# Control.net
KiCad netlist of a schematic drawn in EAGLE
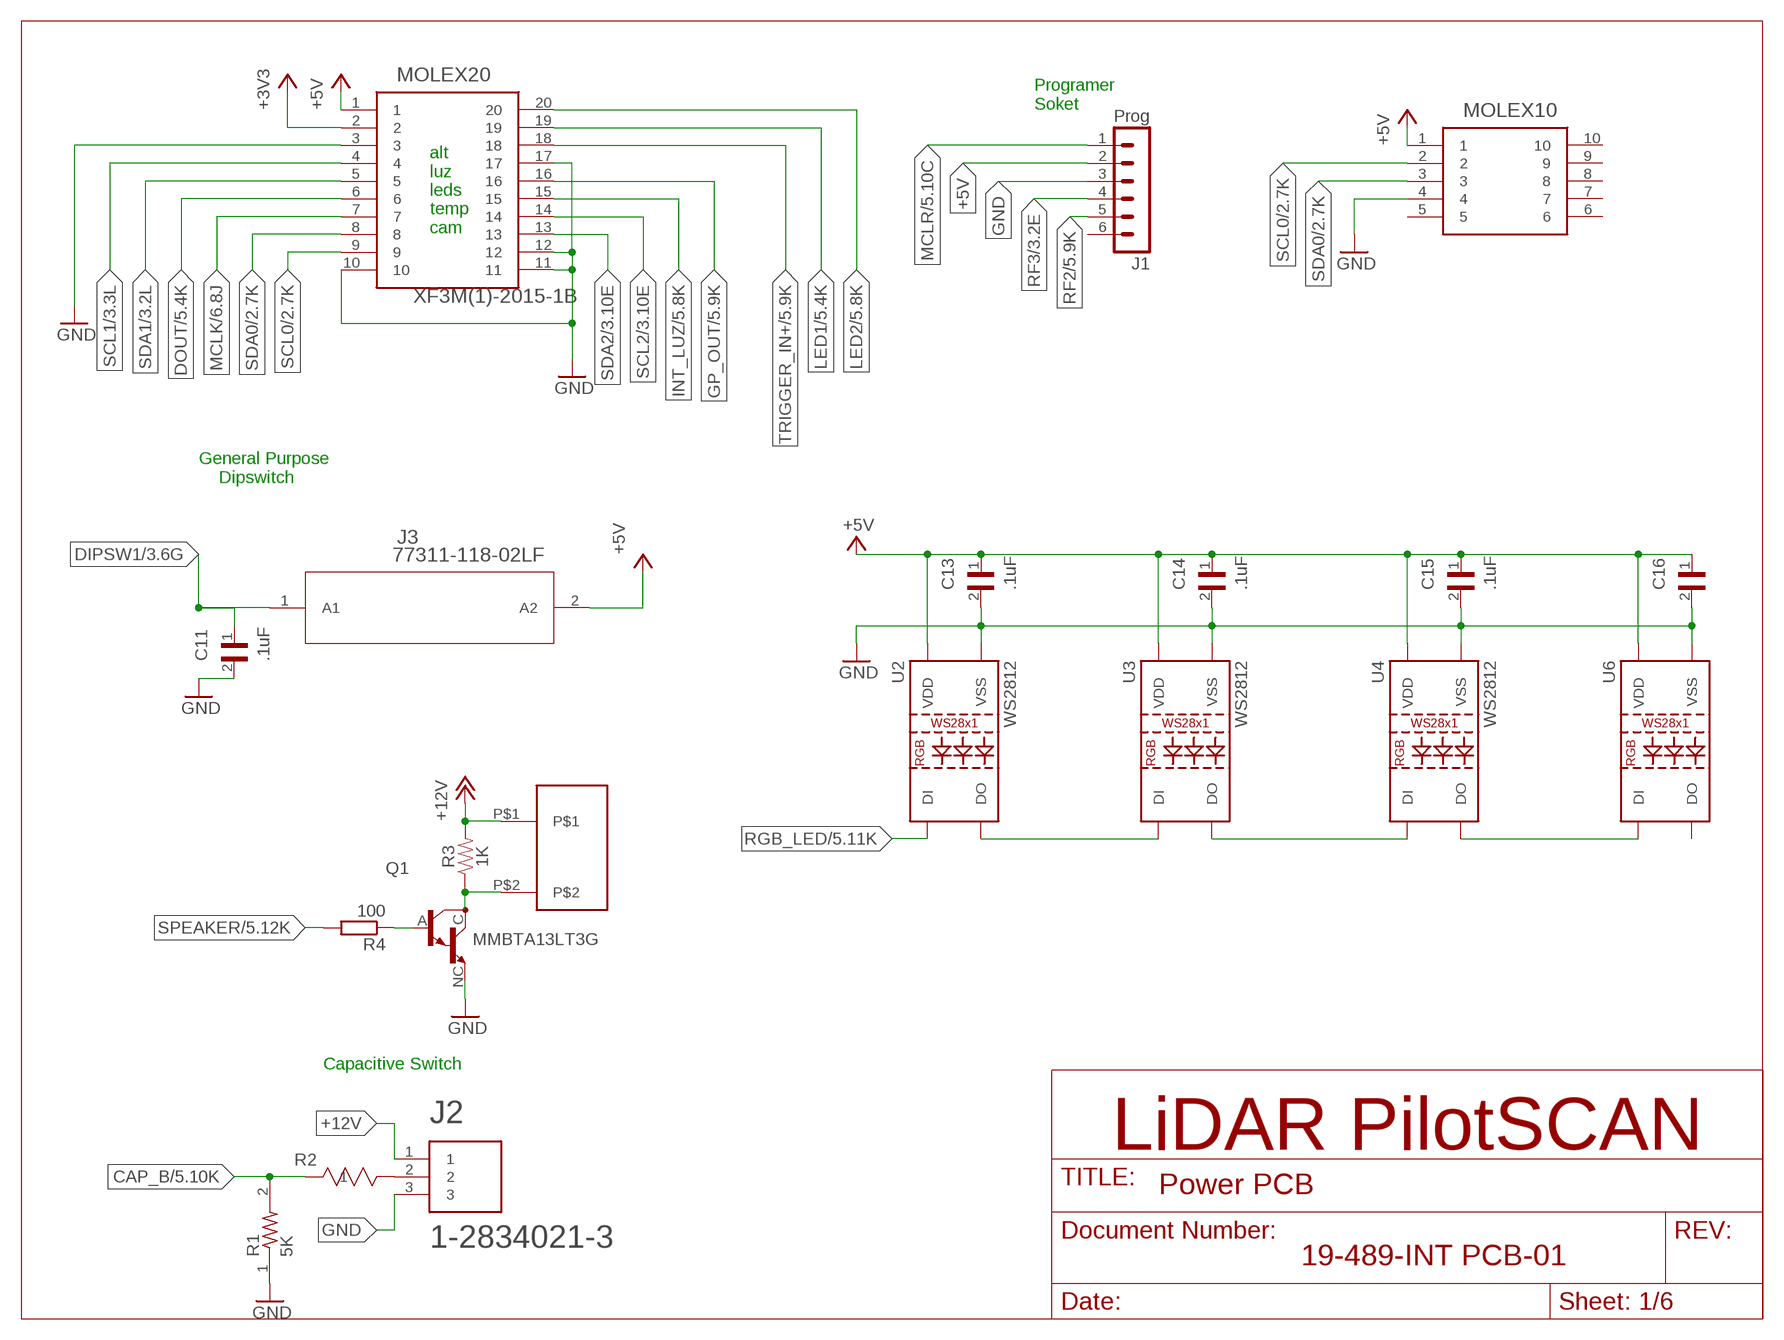
[diagram p0: schematic, sheet 1]
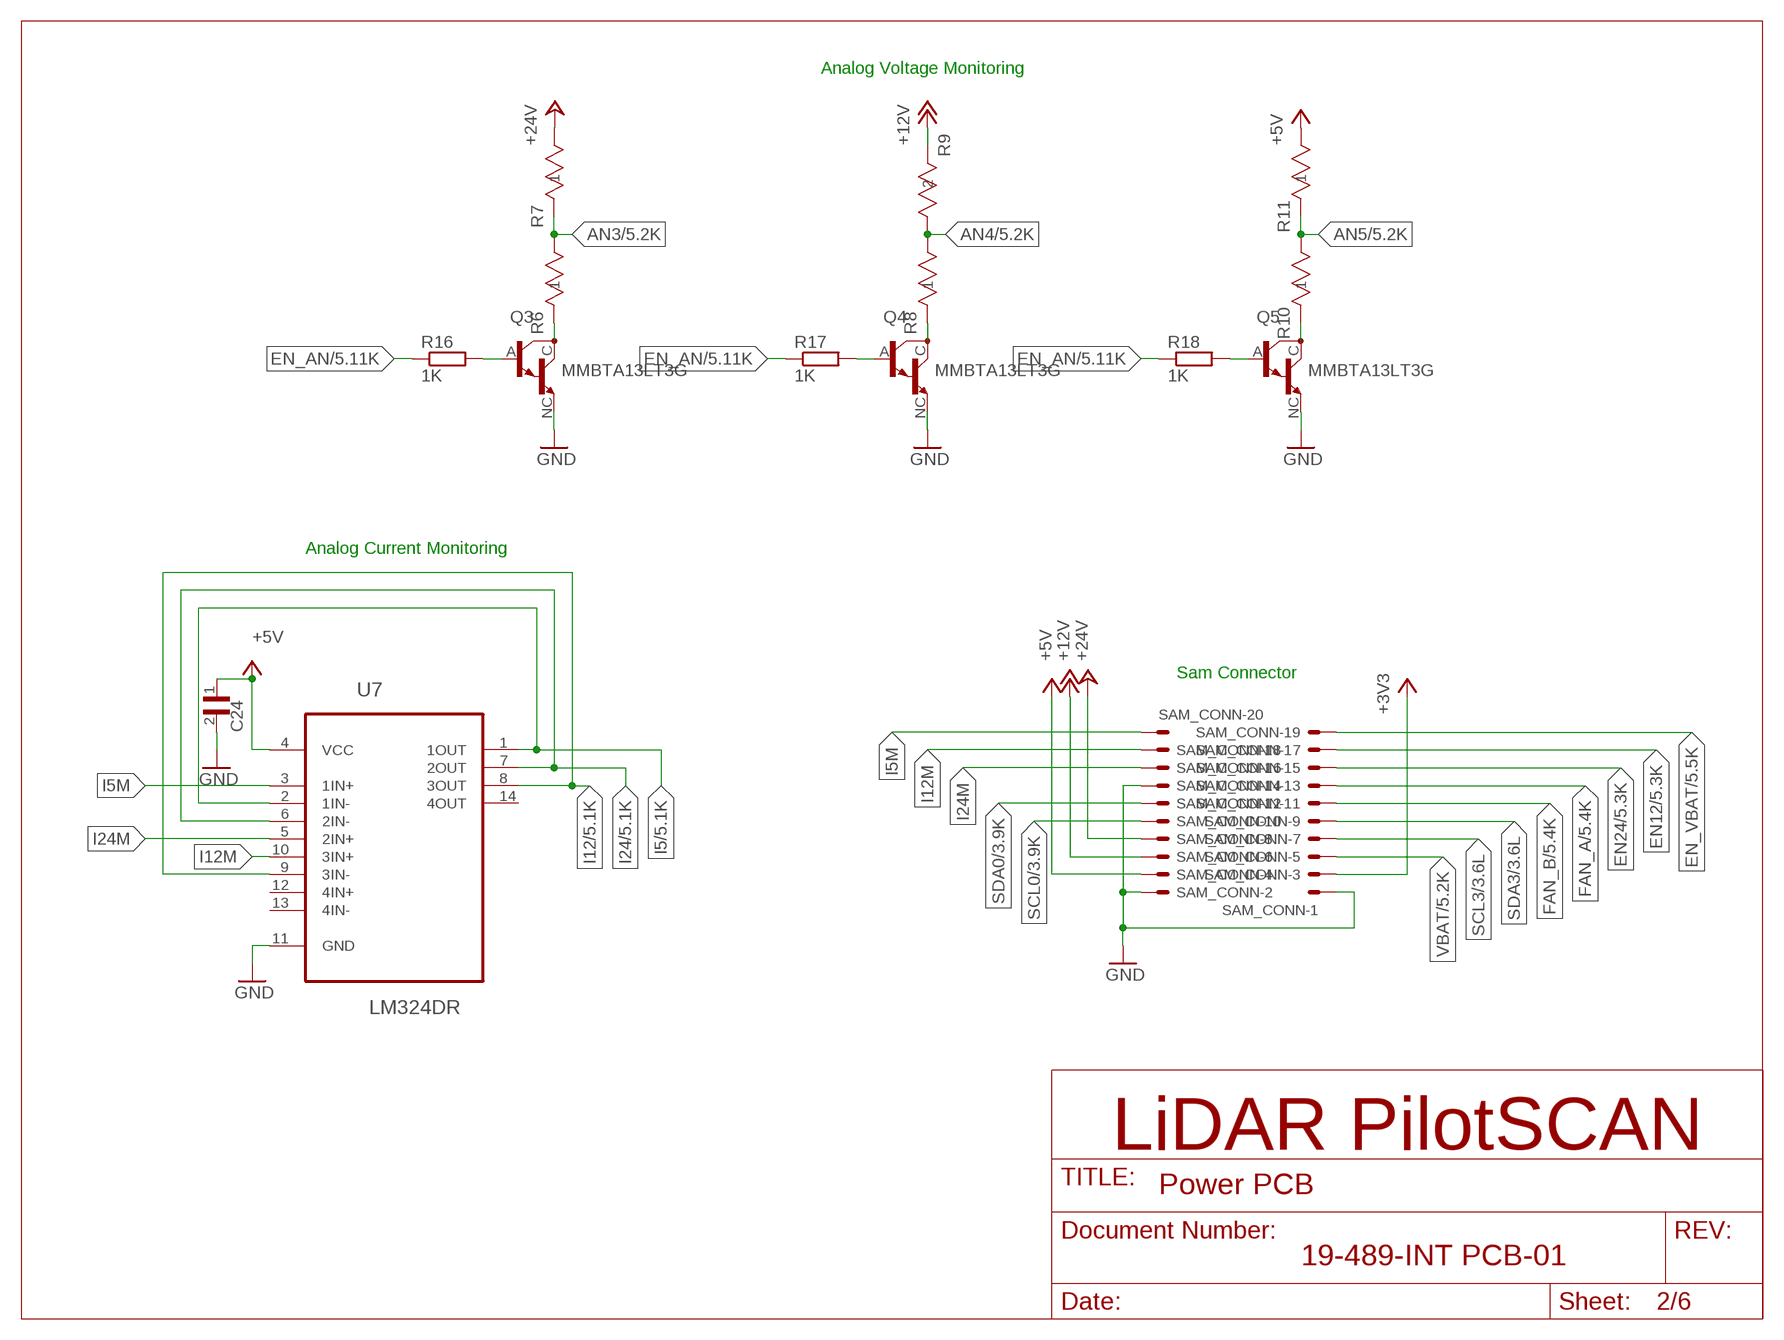
[diagram p1: schematic, sheet 2]
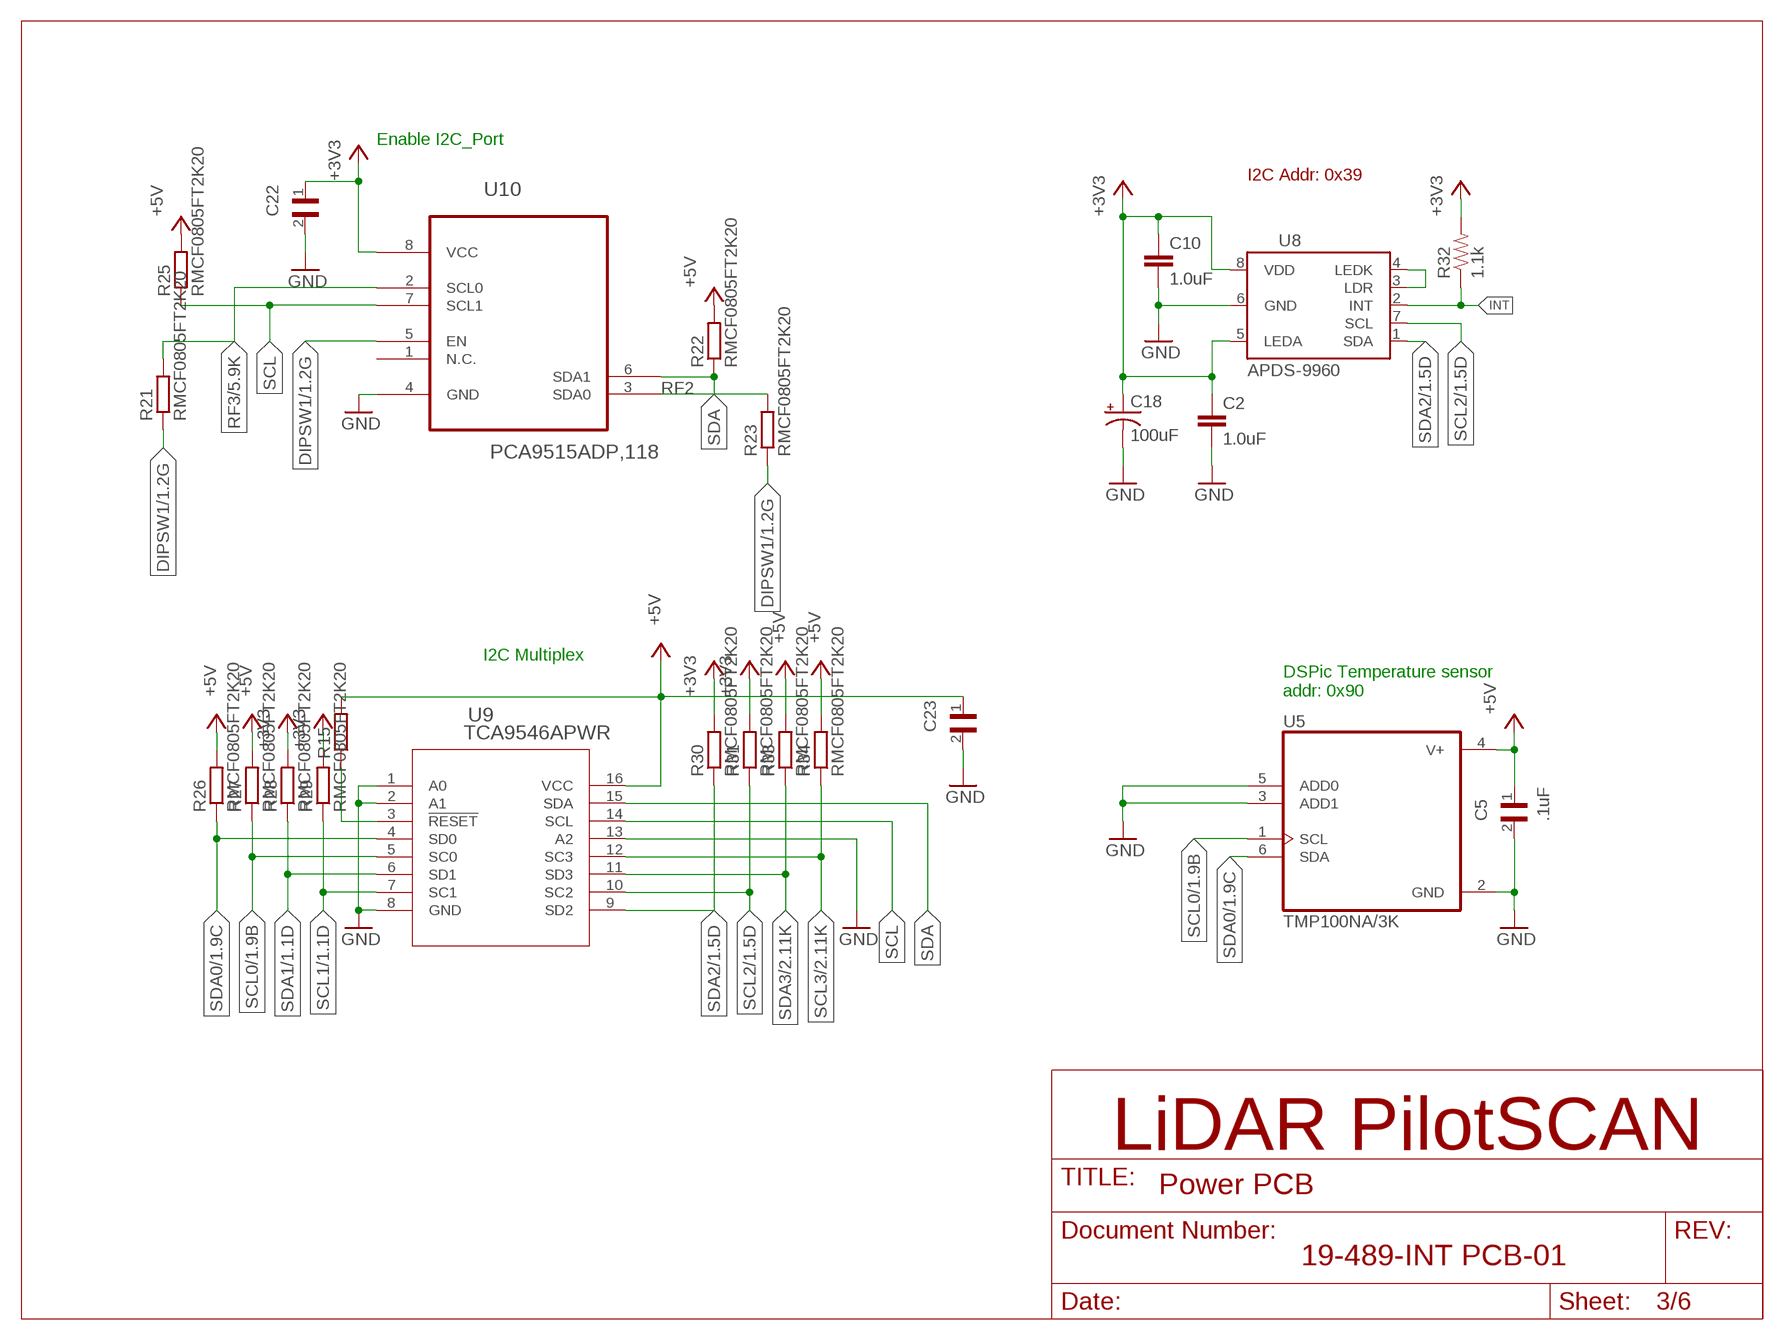
[diagram p2: schematic, sheet 3]
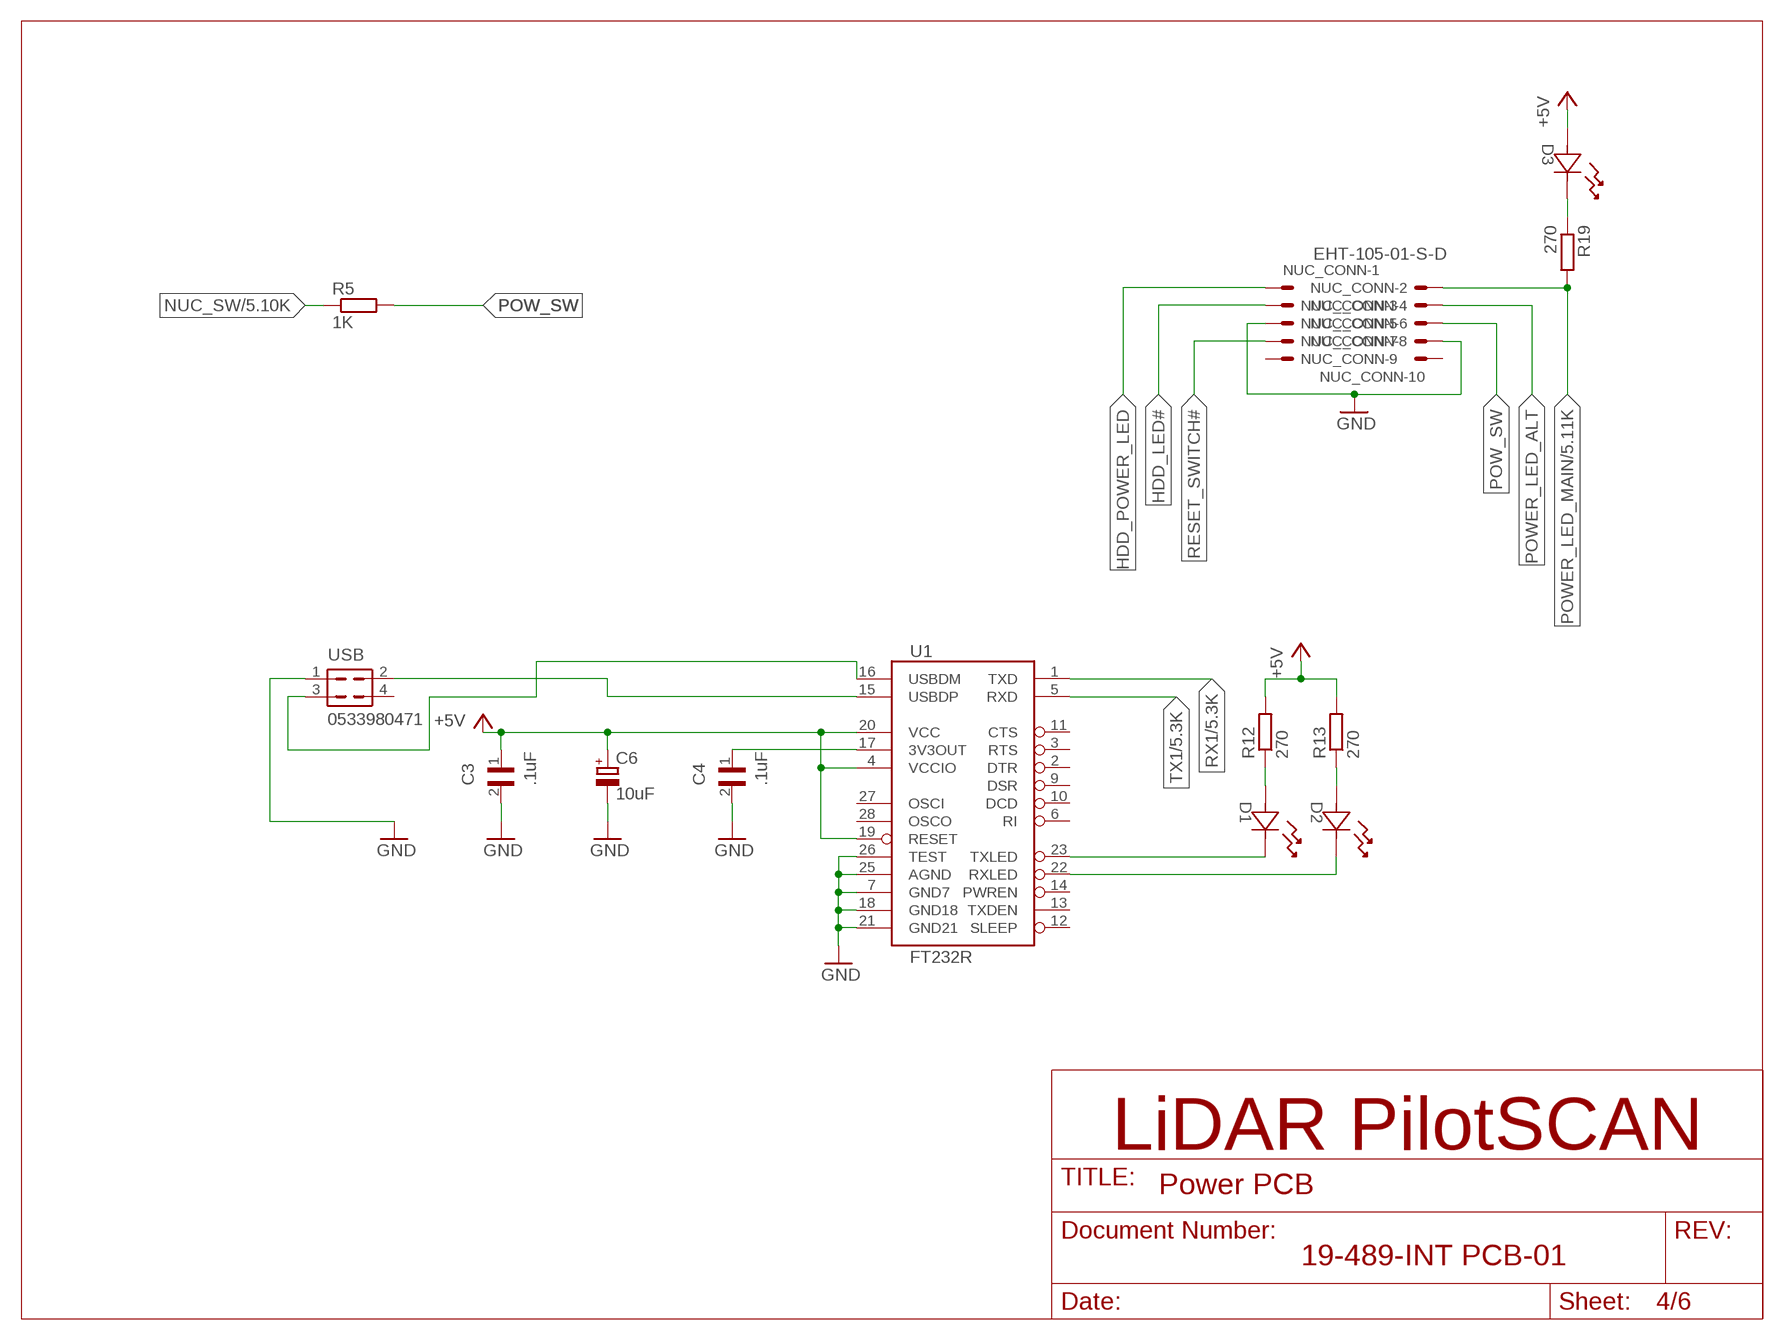
[diagram p3: schematic, sheet 4]
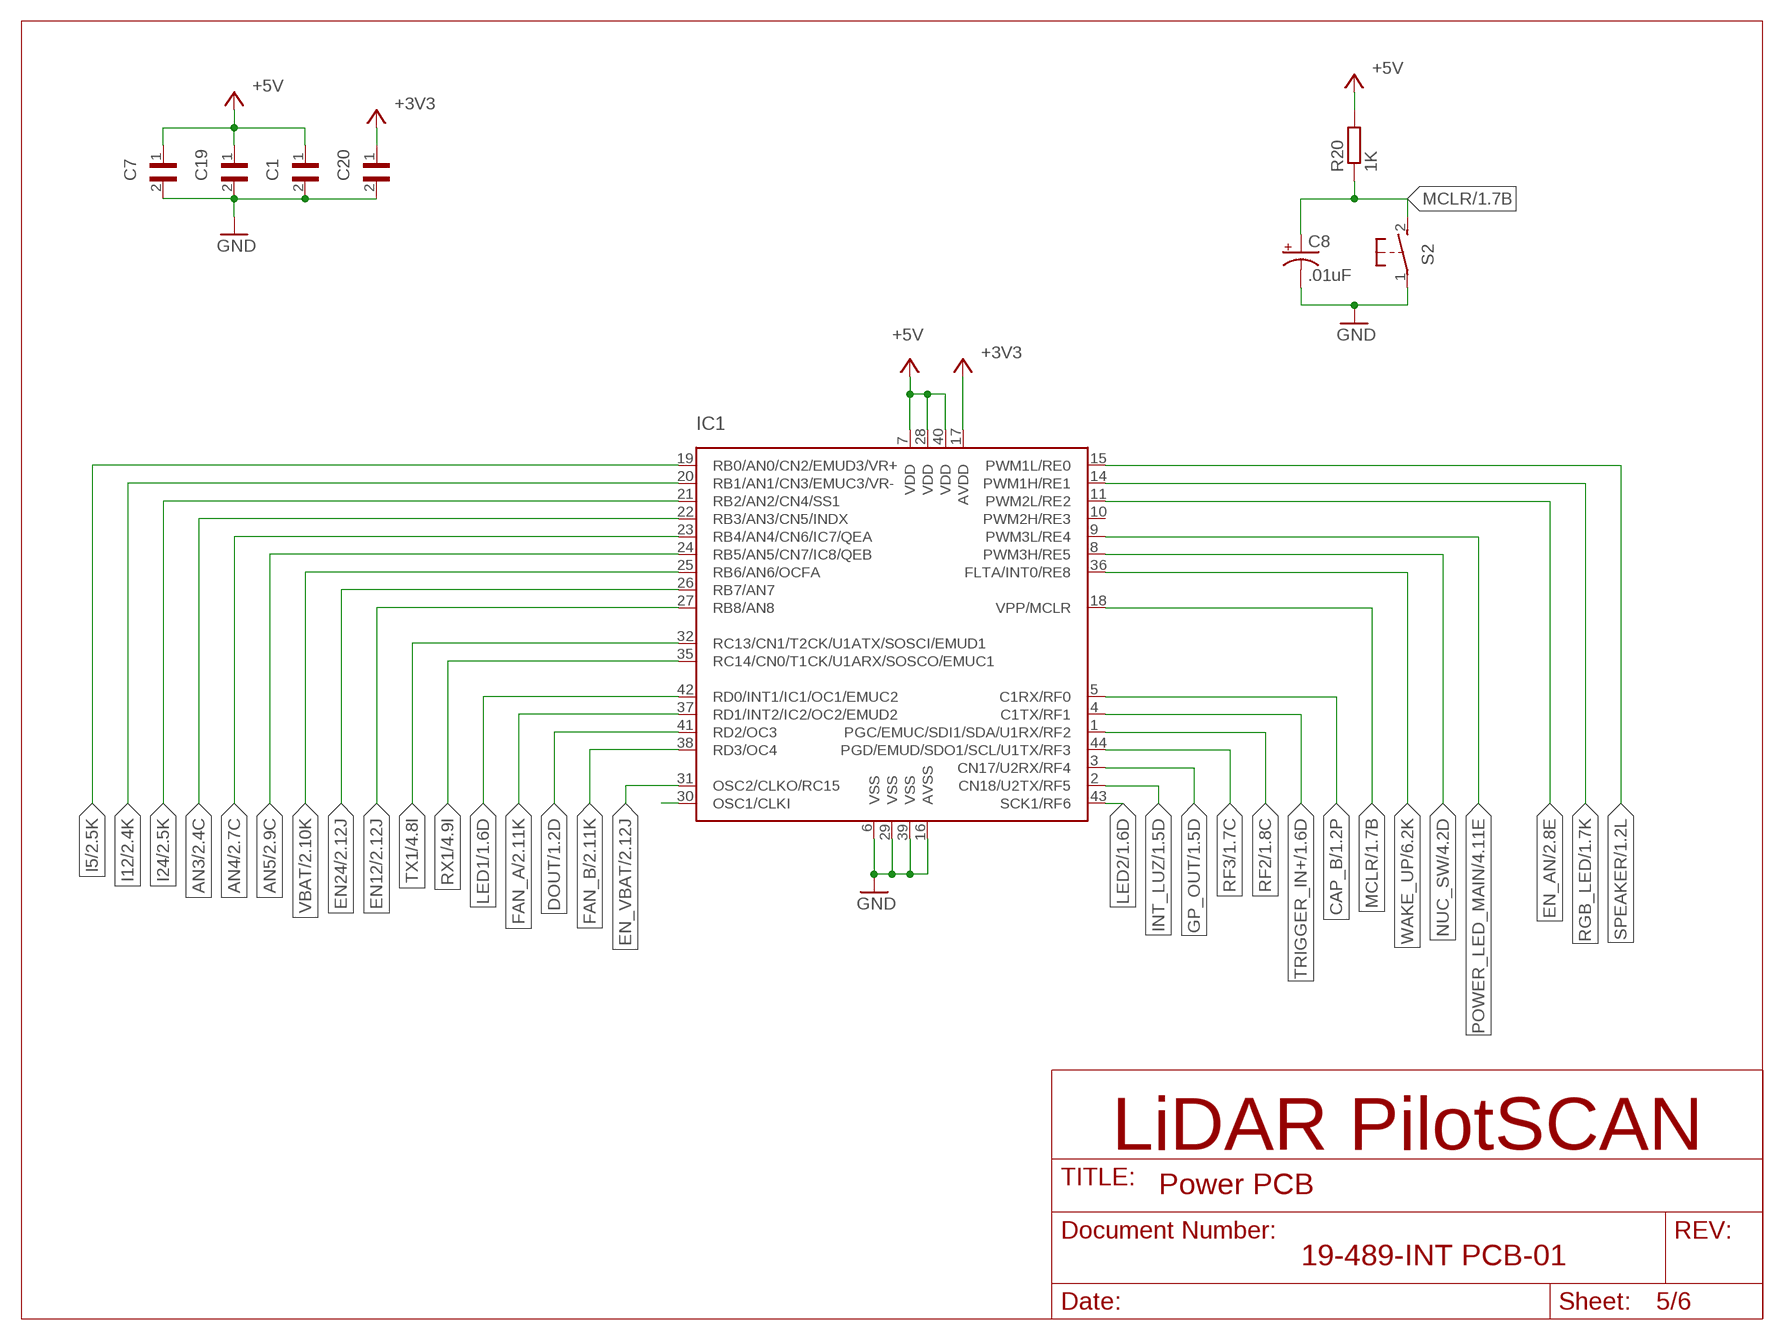
[diagram p4: schematic, sheet 5]
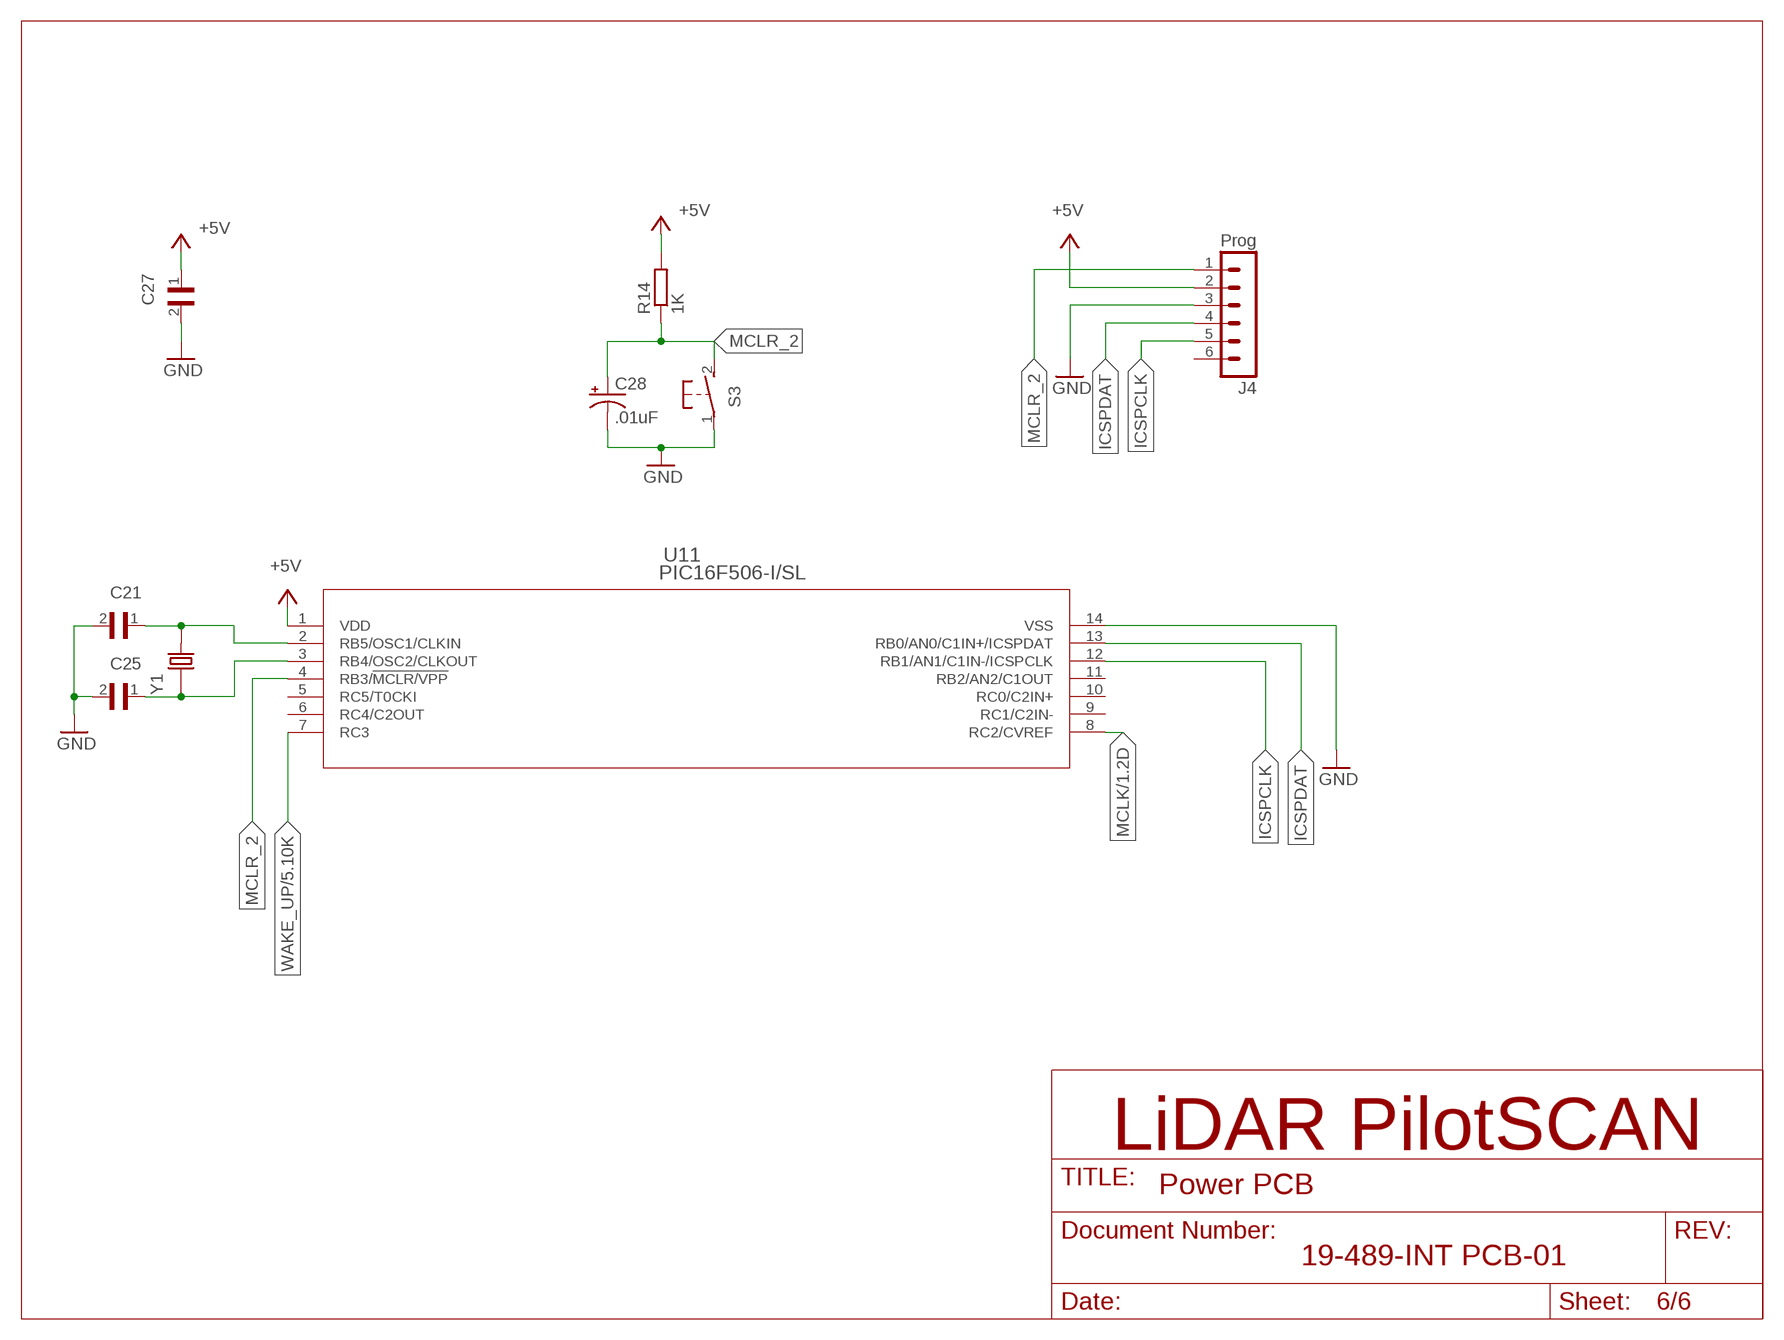
[diagram p5: schematic, sheet 6]

(export (version "E")
  (design (tool "Eeschema 10.0.6"))
  (components
    (comp (ref "C3")
      (value ".1uF")
      (footprint "eagle-import:CAPC2012X140N")
      (fields (field (name "MF") "AVX") (field (name "MP") "08056C104JAZ2A"))
      (libsource (lib "eagle-import") (part "08056C104JAZ2A"))
    )
    (comp (ref "C4")
      (value ".1uF")
      (footprint "eagle-import:CAPC2012X140N")
      (fields (field (name "MF") "AVX") (field (name "MP") "08056C104JAZ2A"))
      (libsource (lib "eagle-import") (part "08056C104JAZ2A"))
    )
    (comp (ref "C6")
      (value "10uF")
      (footprint "eagle-import:E1,8-4")
      (libsource (lib "eagle-import") (part "CPOL-EUE1.8-4"))
    )
    (comp (ref "D1")
      (value "TLMS1100-GS08")
      (footprint "eagle-import:LED_VISHAY_TLMX1100")
      (fields (field (name "MANUFACTURER_PART_NUMBER") "TLMS1100GS08"))
      (libsource (lib "eagle-import") (part "TLMS1100-GS08"))
    )
    (comp (ref "D2")
      (value "TLMS1100-GS08")
      (footprint "eagle-import:LED_VISHAY_TLMX1100")
      (fields (field (name "MANUFACTURER_PART_NUMBER") "TLMS1100GS08"))
      (libsource (lib "eagle-import") (part "TLMS1100-GS08"))
    )
    (comp (ref "D3")
      (value "TLMS1100-GS08")
      (footprint "eagle-import:LED_VISHAY_TLMX1100")
      (fields (field (name "MANUFACTURER_PART_NUMBER") "TLMS1100GS08"))
      (libsource (lib "eagle-import") (part "TLMS1100-GS08"))
    )
    (comp (ref "NUC_CONN")
      (value "EHT-105-01-S-D")
      (footprint "eagle-import:332-10")
      (libsource (lib "eagle-import") (part "EHT-105-01-S-D"))
    )
    (comp (ref "R5")
      (value "1K")
      (footprint "eagle-import:RMCF0805FT1K00")
      (libsource (lib "eagle-import") (part "RMCF0805FT1K00"))
    )
    (comp (ref "R12")
      (value "270")
      (footprint "eagle-import:RMCF0805JT270R")
      (libsource (lib "eagle-import") (part "RMCF0805JT270R"))
    )
    (comp (ref "R13")
      (value "270")
      (footprint "eagle-import:RMCF0805JT270R")
      (libsource (lib "eagle-import") (part "RMCF0805JT270R"))
    )
    (comp (ref "R19")
      (value "270")
      (footprint "eagle-import:RMCF0805JT270R")
      (libsource (lib "eagle-import") (part "RMCF0805JT270R"))
    )
    (comp (ref "U1")
      (value "FT232R")
      (footprint "eagle-import:SSOP28DB")
      (libsource (lib "eagle-import") (part "FT232RLSSOP"))
    )
    (comp (ref "USB")
      (value "0533980471")
      (footprint "eagle-import:0533980471")
      (libsource (lib "eagle-import") (part "0533980471"))
    )
    (comp (ref "C2")
      (value "1.0uF")
      (footprint "eagle-import:0603-CAP")
      (libsource (lib "eagle-import") (part "1.0UF-16V-10%(0603)"))
    )
    (comp (ref "C5")
      (value ".1uF")
      (footprint "eagle-import:CAPC2012X140N")
      (fields (field (name "MF") "AVX") (field (name "MP") "08056C104JAZ2A"))
      (libsource (lib "eagle-import") (part "08056C104JAZ2A"))
    )
    (comp (ref "C10")
      (value "1.0uF")
      (footprint "eagle-import:0603-CAP")
      (libsource (lib "eagle-import") (part "1.0UF-16V-10%(0603)"))
    )
    (comp (ref "C18")
      (value "100uF")
      (footprint "eagle-import:EIA7343")
      (libsource (lib "eagle-import") (part "100UF-10V-10%(TANT)"))
    )
    (comp (ref "C22")
      (value "08056C104JAZ2A")
      (footprint "eagle-import:CAPC2012X140N")
      (fields (field (name "MF") "AVX"))
      (libsource (lib "eagle-import") (part "08056C104JAZ2A"))
    )
    (comp (ref "C23")
      (value "08056C104JAZ2A")
      (footprint "eagle-import:CAPC2012X140N")
      (fields (field (name "MF") "AVX"))
      (libsource (lib "eagle-import") (part "08056C104JAZ2A"))
    )
    (comp (ref "R15")
      (value "RMCF0805FT2K20")
      (footprint "eagle-import:RMCF0805FT2K20")
      (libsource (lib "eagle-import") (part "RMCF0805FT2K20"))
    )
    (comp (ref "R21")
      (value "RMCF0805FT2K20")
      (footprint "eagle-import:RMCF0805FT2K20")
      (libsource (lib "eagle-import") (part "RMCF0805FT2K20"))
    )
    (comp (ref "R22")
      (value "RMCF0805FT2K20")
      (footprint "eagle-import:RMCF0805FT2K20")
      (libsource (lib "eagle-import") (part "RMCF0805FT2K20"))
    )
    (comp (ref "R23")
      (value "RMCF0805FT2K20")
      (footprint "eagle-import:RMCF0805FT2K20")
      (libsource (lib "eagle-import") (part "RMCF0805FT2K20"))
    )
    (comp (ref "R25")
      (value "RMCF0805FT2K20")
      (footprint "eagle-import:RMCF0805FT2K20")
      (libsource (lib "eagle-import") (part "RMCF0805FT2K20"))
    )
    (comp (ref "R26")
      (value "RMCF0805FT2K20")
      (footprint "eagle-import:RMCF0805FT2K20")
      (libsource (lib "eagle-import") (part "RMCF0805FT2K20"))
    )
    (comp (ref "R27")
      (value "RMCF0805FT2K20")
      (footprint "eagle-import:RMCF0805FT2K20")
      (libsource (lib "eagle-import") (part "RMCF0805FT2K20"))
    )
    (comp (ref "R28")
      (value "RMCF0805FT2K20")
      (footprint "eagle-import:RMCF0805FT2K20")
      (libsource (lib "eagle-import") (part "RMCF0805FT2K20"))
    )
    (comp (ref "R29")
      (value "RMCF0805FT2K20")
      (footprint "eagle-import:RMCF0805FT2K20")
      (libsource (lib "eagle-import") (part "RMCF0805FT2K20"))
    )
    (comp (ref "R30")
      (value "RMCF0805FT2K20")
      (footprint "eagle-import:RMCF0805FT2K20")
      (libsource (lib "eagle-import") (part "RMCF0805FT2K20"))
    )
    (comp (ref "R31")
      (value "RMCF0805FT2K20")
      (footprint "eagle-import:RMCF0805FT2K20")
      (libsource (lib "eagle-import") (part "RMCF0805FT2K20"))
    )
    (comp (ref "R32")
      (value "1.1k")
      (footprint "eagle-import:0603-RES")
      (libsource (lib "eagle-import") (part "10KOHM1/10W1%(0603)0603"))
    )
    (comp (ref "R33")
      (value "RMCF0805FT2K20")
      (footprint "eagle-import:RMCF0805FT2K20")
      (libsource (lib "eagle-import") (part "RMCF0805FT2K20"))
    )
    (comp (ref "R34")
      (value "RMCF0805FT2K20")
      (footprint "eagle-import:RMCF0805FT2K20")
      (libsource (lib "eagle-import") (part "RMCF0805FT2K20"))
    )
    (comp (ref "U5")
      (value "TMP100NA/3K")
      (footprint "eagle-import:TMP100NA_3K")
      (fields (field (name "MF") "Texas Instruments"))
      (libsource (lib "eagle-import") (part "TMP100NA/3K"))
    )
    (comp (ref "U8")
      (value "APDS-9960")
      (footprint "eagle-import:APDS-9960")
      (libsource (lib "eagle-import") (part "APDS-9960"))
    )
    (comp (ref "U9")
      (value "TCA9546APWR")
      (footprint "eagle-import:PW16")
      (libsource (lib "eagle-import") (part "TCA9546APWR"))
    )
    (comp (ref "U10")
      (value "PCA9515ADP,118")
      (footprint "eagle-import:SOP65P490X110-8N")
      (fields (field (name "MF") "NXP USA"))
      (libsource (lib "eagle-import") (part "PCA9515ADP,118"))
    )
    (comp (ref "C24")
      (value "08056C104JAZ2A")
      (footprint "eagle-import:CAPC2012X140N")
      (fields (field (name "MF") "AVX"))
      (libsource (lib "eagle-import") (part "08056C104JAZ2A"))
    )
    (comp (ref "Q3")
      (value "MMBTA13LT3G")
      (footprint "eagle-import:MMBTA13LT3G")
      (libsource (lib "eagle-import") (part "MMBTA13LT3G"))
    )
    (comp (ref "Q4")
      (value "MMBTA13LT3G")
      (footprint "eagle-import:MMBTA13LT3G")
      (libsource (lib "eagle-import") (part "MMBTA13LT3G"))
    )
    (comp (ref "Q5")
      (value "MMBTA13LT3G")
      (footprint "eagle-import:MMBTA13LT3G")
      (libsource (lib "eagle-import") (part "MMBTA13LT3G"))
    )
    (comp (ref "R6")
      (value "1K8")
      (footprint "eagle-import:RES_RC0201_P6XP3")
      (fields (field (name "MANUFACTURER_PART_NUMBER") "RC0201JR071K8L"))
      (libsource (lib "eagle-import") (part "RC0201JR-071K8L"))
    )
    (comp (ref "R7")
      (value "18K")
      (footprint "eagle-import:RES_RC0201_P6XP3")
      (fields (field (name "MANUFACTURER_PART_NUMBER") "RC0201JR071K8L"))
      (libsource (lib "eagle-import") (part "RMCF0603JT18K0_RC0201JR-071K8L"))
    )
    (comp (ref "R8")
      (value "1K8")
      (footprint "eagle-import:RES_RC0201_P6XP3")
      (fields (field (name "MANUFACTURER_PART_NUMBER") "RC0201JR071K8L"))
      (libsource (lib "eagle-import") (part "RC0201JR-071K8L"))
    )
    (comp (ref "R9")
      (value "8K2")
      (footprint "eagle-import:RES0805_CRG_TYCO-L")
      (fields (field (name "MANUFACTURER_PART_NUMBER") "CRG0805F8K2"))
      (libsource (lib "eagle-import") (part "CRG0805F8K2RES0805_CRG_TYCO-L"))
    )
    (comp (ref "R10")
      (value "1K8")
      (footprint "eagle-import:RES_RC0201_P6XP3")
      (fields (field (name "MANUFACTURER_PART_NUMBER") "RC0201JR071K8L"))
      (libsource (lib "eagle-import") (part "RC0201JR-071K8L"))
    )
    (comp (ref "R11")
      (value "1K5")
      (footprint "eagle-import:YAG_R0201")
      (fields (field (name "MANUFACTURER_PART_NUMBER") "RC0201JR071K5L"))
      (libsource (lib "eagle-import") (part "RC0201JR-071K5L"))
    )
    (comp (ref "R16")
      (value "1K")
      (footprint "eagle-import:RMCF0805FT1K00")
      (libsource (lib "eagle-import") (part "RMCF0805FT1K00"))
    )
    (comp (ref "R17")
      (value "1K")
      (footprint "eagle-import:RMCF0805FT1K00")
      (libsource (lib "eagle-import") (part "RMCF0805FT1K00"))
    )
    (comp (ref "R18")
      (value "1K")
      (footprint "eagle-import:RMCF0805FT1K00")
      (libsource (lib "eagle-import") (part "RMCF0805FT1K00"))
    )
    (comp (ref "SAM_CONN")
      (value "IPT1-110-01-L-D")
      (footprint "eagle-import:IPT1-110-01-L-D")
      (libsource (lib "eagle-import") (part "IPT1-110-01-L-D"))
    )
    (comp (ref "U7")
      (value "LM324DR")
      (footprint "eagle-import:SOIC127P600X175-14N")
      (fields (field (name "MF") "Texas Instruments") (field (name "SPICEPREFIX") "X"))
      (libsource (lib "eagle-import") (part "LM324DR"))
    )
    (comp (ref "C1")
      (value "08056C104JAZ2A")
      (footprint "eagle-import:CAPC2012X140N")
      (fields (field (name "MF") "AVX"))
      (libsource (lib "eagle-import") (part "08056C104JAZ2A"))
    )
    (comp (ref "C7")
      (value "08056C104JAZ2A")
      (footprint "eagle-import:CAPC2012X140N")
      (fields (field (name "MF") "AVX"))
      (libsource (lib "eagle-import") (part "08056C104JAZ2A"))
    )
    (comp (ref "C8")
      (value ".01uF")
      (footprint "eagle-import:CL03A104KQ3NNNC")
      (libsource (lib "eagle-import") (part "CL03A104KQ3NNNC"))
    )
    (comp (ref "C19")
      (value "08056C104JAZ2A")
      (footprint "eagle-import:CAPC2012X140N")
      (fields (field (name "MF") "AVX"))
      (libsource (lib "eagle-import") (part "08056C104JAZ2A"))
    )
    (comp (ref "C20")
      (value "08056C104JAZ2A")
      (footprint "eagle-import:CAPC2012X140N")
      (fields (field (name "MF") "AVX"))
      (libsource (lib "eagle-import") (part "08056C104JAZ2A"))
    )
    (comp (ref "IC1")
      (value "DSPIC30F4011/PT")
      (footprint "eagle-import:TQFP44")
      (libsource (lib "eagle-import") (part "DSPIC30F4011/PT"))
    )
    (comp (ref "R20")
      (value "1K")
      (footprint "eagle-import:RMCF0805FT1K00")
      (libsource (lib "eagle-import") (part "RMCF0805FT1K00"))
    )
    (comp (ref "S2")
      (value "DTSM-3")
      (footprint "eagle-import:DTSM-3")
      (libsource (lib "eagle-import") (part "DTSM-3"))
    )
    (comp (ref "C21")
      (value "C0603C150M8GACTU")
      (footprint "eagle-import:CAPC1608X90")
      (fields (field (name "DIGI-KEY_PART_NUMBER") "399-9005-1-ND") (field (name "MF") "KEMET"))
      (libsource (lib "eagle-import") (part "C0603C150M8GACTU"))
    )
    (comp (ref "C25")
      (value "C0603C150M8GACTU")
      (footprint "eagle-import:CAPC1608X90")
      (fields (field (name "DIGI-KEY_PART_NUMBER") "399-9005-1-ND") (field (name "MF") "KEMET"))
      (libsource (lib "eagle-import") (part "C0603C150M8GACTU"))
    )
    (comp (ref "C27")
      (value "08056C104JAZ2A")
      (footprint "eagle-import:CAPC2012X140N")
      (fields (field (name "MF") "AVX"))
      (libsource (lib "eagle-import") (part "08056C104JAZ2A"))
    )
    (comp (ref "C28")
      (value ".01uF")
      (footprint "eagle-import:CL03A104KQ3NNNC")
      (libsource (lib "eagle-import") (part "CL03A104KQ3NNNC"))
    )
    (comp (ref "J4")
      (value "Prog")
      (footprint "eagle-import:MA06-1")
      (libsource (lib "eagle-import") (part "MA06-1"))
    )
    (comp (ref "R14")
      (value "1K")
      (footprint "eagle-import:RMCF0805FT1K00")
      (libsource (lib "eagle-import") (part "RMCF0805FT1K00"))
    )
    (comp (ref "S3")
      (value "DTSM-3")
      (footprint "eagle-import:DTSM-3")
      (libsource (lib "eagle-import") (part "DTSM-3"))
    )
    (comp (ref "U11")
      (value "PIC16F506-I/SL")
      (footprint "eagle-import:SOIC14-N_MC")
      (fields (field (name "MANUFACTURER_PART_NUMBER") "PIC16F506ISL"))
      (libsource (lib "eagle-import") (part "PIC16F506-I/SL"))
    )
    (comp (ref "Y1")
      (value "ECS-10-13-1XH")
      (footprint "eagle-import:XTAL_ECS-10-13-1XH")
      (fields (field (name "DIGI-KEY_PART_NUMBER") "X999-ND") (field (name "MF") "ECS Inc."))
      (libsource (lib "eagle-import") (part "ECS-10-13-1XH"))
    )
    (comp (ref "BUZZ1")
      (value "PS1240P02BT")
      (footprint "eagle-import:PS1240P02BT")
      (fields (field (name "MF") "TDK"))
      (libsource (lib "eagle-import") (part "PS1240P02BT"))
    )
    (comp (ref "C11")
      (value ".1uF")
      (footprint "eagle-import:CAPC2012X140N")
      (fields (field (name "MF") "AVX") (field (name "MP") "08056C104JAZ2A"))
      (libsource (lib "eagle-import") (part "08056C104JAZ2A"))
    )
    (comp (ref "C13")
      (value ".1uF")
      (footprint "eagle-import:CAPC2012X140N")
      (fields (field (name "MF") "AVX") (field (name "MP") "08056C104JAZ2A"))
      (libsource (lib "eagle-import") (part "08056C104JAZ2A"))
    )
    (comp (ref "C14")
      (value ".1uF")
      (footprint "eagle-import:CAPC2012X140N")
      (fields (field (name "MF") "AVX") (field (name "MP") "08056C104JAZ2A"))
      (libsource (lib "eagle-import") (part "08056C104JAZ2A"))
    )
    (comp (ref "C15")
      (value ".1uF")
      (footprint "eagle-import:CAPC2012X140N")
      (fields (field (name "MF") "AVX") (field (name "MP") "08056C104JAZ2A"))
      (libsource (lib "eagle-import") (part "08056C104JAZ2A"))
    )
    (comp (ref "C16")
      (value ".1uF")
      (footprint "eagle-import:CAPC2012X140N")
      (fields (field (name "MF") "AVX") (field (name "MP") "08056C104JAZ2A"))
      (libsource (lib "eagle-import") (part "08056C104JAZ2A"))
    )
    (comp (ref "J1")
      (value "Prog")
      (footprint "eagle-import:MA06-1")
      (libsource (lib "eagle-import") (part "MA06-1"))
    )
    (comp (ref "J2")
      (value "1-2834021-3")
      (footprint "eagle-import:CONN_1-2834021-3")
      (fields (field (name "DIGI-KEY_PART_NUMBER") "A123845-ND") (field (name "MF") "TE Connectivity"))
      (libsource (lib "eagle-import") (part "1-2834021-3"))
    )
    (comp (ref "J3")
      (value "77311-118-02LF")
      (footprint "eagle-import:77311-118-02LF")
      (fields (field (name "MANUFACTURER_PART_NUMBER") "7731111802LF"))
      (libsource (lib "eagle-import") (part "77311-118-02LF"))
    )
    (comp (ref "MOLEX10")
      (value "522071060")
      (footprint "eagle-import:522071060")
      (fields (field (name "MF") "Molex") (field (name "MP") "52207-1485"))
      (libsource (lib "eagle-import") (part "522071060"))
    )
    (comp (ref "MOLEX20")
      (value "XF3M(1)-2015-1B")
      (footprint "eagle-import:XF3M(1)-2015-1B")
      (fields (field (name "MF") "Molex") (field (name "MP") "52207-1485"))
      (libsource (lib "eagle-import") (part "XF3M(1)-2015-1B"))
    )
    (comp (ref "Q1")
      (value "MMBTA13LT3G")
      (footprint "eagle-import:MMBTA13LT3G")
      (libsource (lib "eagle-import") (part "MMBTA13LT3G"))
    )
    (comp (ref "R1")
      (value "5K")
      (footprint "eagle-import:RESC2012X60")
      (fields
        (field (name "DIGI-KEY_PART_NUMBER") "541-4321-1-ND")
        (field (name "MF") "Vishay")
        (field (name "MP") "CRCW08055K00FKTA")
      )
      (libsource (lib "eagle-import") (part "CRCW08055K00FKTA"))
    )
    (comp (ref "R2")
      (value "6K8")
      (footprint "eagle-import:RES_RC0201_P6XP3")
      (fields (field (name "MANUFACTURER_PART_NUMBER") "RC0201FR076K8L"))
      (libsource (lib "eagle-import") (part "RC0201FR-076K8L"))
    )
    (comp (ref "R3")
      (value "1K")
      (footprint "eagle-import:AXIAL-0.3")
      (libsource (lib "eagle-import") (part "10MOHM-HORIZ-1/4W-5%"))
    )
    (comp (ref "R4")
      (value "100")
      (footprint "eagle-import:RMCF0805JT270R")
      (libsource (lib "eagle-import") (part "RMCF0805JT270R"))
    )
    (comp (ref "U2")
      (value "WS2812")
      (footprint "eagle-import:LED-TRICOLOR-5050-IC")
      (libsource (lib "eagle-import") (part "WS2812{dblquote}"))
    )
    (comp (ref "U3")
      (value "WS2812")
      (footprint "eagle-import:LED-TRICOLOR-5050-IC")
      (libsource (lib "eagle-import") (part "WS2812{dblquote}"))
    )
    (comp (ref "U4")
      (value "WS2812")
      (footprint "eagle-import:LED-TRICOLOR-5050-IC")
      (libsource (lib "eagle-import") (part "WS2812{dblquote}"))
    )
    (comp (ref "U6")
      (value "WS2812")
      (footprint "eagle-import:LED-TRICOLOR-5050-IC")
      (libsource (lib "eagle-import") (part "WS2812{dblquote}"))
    )
  )
  (nets
    (net (code "1") (name "+3V3") (class "Default")
      (node (ref "C10") (pin "1") (pinfunction "1_1") (pintype "passive"))
      (node (ref "C18") (pin "A") (pinfunction "+_A") (pintype "passive"))
      (node (ref "C2") (pin "1") (pinfunction "1_1") (pintype "passive"))
      (node (ref "C20") (pin "1") (pinfunction "1_1") (pintype "passive"))
      (node (ref "C22") (pin "1") (pinfunction "1_1") (pintype "passive"))
      (node (ref "IC1") (pin "17") (pinfunction "AVDD_17") (pintype "power_in"))
      (node (ref "MOLEX20") (pin "2") (pinfunction "2_2") (pintype "bidirectional"))
      (node (ref "R28") (pin "2") (pinfunction "2_2") (pintype "passive"))
      (node (ref "R29") (pin "2") (pinfunction "2_2") (pintype "passive"))
      (node (ref "R30") (pin "2") (pinfunction "2_2") (pintype "passive"))
      (node (ref "R31") (pin "2") (pinfunction "2_2") (pintype "passive"))
      (node (ref "R32") (pin "2") (pinfunction "2_2") (pintype "passive"))
      (node (ref "SAM_CONN") (pin "P$3") (pinfunction "S_P$3") (pintype "passive"))
      (node (ref "U10") (pin "8") (pinfunction "VCC_8") (pintype "power_in"))
      (node (ref "U8") (pin "5") (pinfunction "LEDA_5") (pintype "bidirectional"))
      (node (ref "U8") (pin "8") (pinfunction "VDD_8") (pintype "bidirectional"))
    )
    (net (code "2") (name "+5V") (class "Default")
      (node (ref "C1") (pin "1") (pinfunction "1_1") (pintype "passive"))
      (node (ref "C13") (pin "1") (pinfunction "1_1") (pintype "passive"))
      (node (ref "C14") (pin "1") (pinfunction "1_1") (pintype "passive"))
      (node (ref "C15") (pin "1") (pinfunction "1_1") (pintype "passive"))
      (node (ref "C16") (pin "1") (pinfunction "1_1") (pintype "passive"))
      (node (ref "C19") (pin "1") (pinfunction "1_1") (pintype "passive"))
      (node (ref "C23") (pin "1") (pinfunction "1_1") (pintype "passive"))
      (node (ref "C24") (pin "1") (pinfunction "1_1") (pintype "passive"))
      (node (ref "C27") (pin "1") (pinfunction "1_1") (pintype "passive"))
      (node (ref "C3") (pin "1") (pinfunction "1_1") (pintype "passive"))
      (node (ref "C5") (pin "1") (pinfunction "1_1") (pintype "passive"))
      (node (ref "C6") (pin "+") (pinfunction "+_+") (pintype "passive"))
      (node (ref "C7") (pin "1") (pinfunction "1_1") (pintype "passive"))
      (node (ref "D3") (pin "2") (pinfunction "2_2") (pintype "passive"))
      (node (ref "IC1") (pin "28") (pinfunction "VDD_28") (pintype "power_in"))
      (node (ref "IC1") (pin "40") (pinfunction "VDD_40") (pintype "power_in"))
      (node (ref "IC1") (pin "7") (pinfunction "VDD_7") (pintype "power_in"))
      (node (ref "J1") (pin "2") (pinfunction "2_2") (pintype "passive"))
      (node (ref "J3") (pin "2") (pinfunction "A2_2") (pintype "passive"))
      (node (ref "J4") (pin "2") (pinfunction "2_2") (pintype "passive"))
      (node (ref "MOLEX10") (pin "1") (pinfunction "1_1") (pintype "bidirectional"))
      (node (ref "MOLEX20") (pin "1") (pinfunction "1_1") (pintype "bidirectional"))
      (node (ref "R11") (pin "2") (pinfunction "2_2") (pintype "passive"))
      (node (ref "R12") (pin "2") (pinfunction "2_2") (pintype "passive"))
      (node (ref "R13") (pin "2") (pinfunction "2_2") (pintype "passive"))
      (node (ref "R14") (pin "2") (pinfunction "2_2") (pintype "passive"))
      (node (ref "R15") (pin "2") (pinfunction "2_2") (pintype "passive"))
      (node (ref "R20") (pin "2") (pinfunction "2_2") (pintype "passive"))
      (node (ref "R22") (pin "2") (pinfunction "2_2") (pintype "passive"))
      (node (ref "R25") (pin "2") (pinfunction "2_2") (pintype "passive"))
      (node (ref "R26") (pin "2") (pinfunction "2_2") (pintype "passive"))
      (node (ref "R27") (pin "2") (pinfunction "2_2") (pintype "passive"))
      (node (ref "R33") (pin "2") (pinfunction "2_2") (pintype "passive"))
      (node (ref "R34") (pin "2") (pinfunction "2_2") (pintype "passive"))
      (node (ref "SAM_CONN") (pin "P$4") (pinfunction "S_P$4") (pintype "passive"))
      (node (ref "U1") (pin "19") (pinfunction "RESET_19") (pintype "input"))
      (node (ref "U1") (pin "20") (pinfunction "VCC_20") (pintype "power_in"))
      (node (ref "U1") (pin "4") (pinfunction "VCCIO_4") (pintype "power_in"))
      (node (ref "U11") (pin "1") (pinfunction "VDD_1") (pintype "passive"))
      (node (ref "U2") (pin "3") (pinfunction "VDD_3") (pintype "bidirectional"))
      (node (ref "U2") (pin "5") (pinfunction "VDD_5") (pintype "bidirectional"))
      (node (ref "U3") (pin "3") (pinfunction "VDD_3") (pintype "bidirectional"))
      (node (ref "U3") (pin "5") (pinfunction "VDD_5") (pintype "bidirectional"))
      (node (ref "U4") (pin "3") (pinfunction "VDD_3") (pintype "bidirectional"))
      (node (ref "U4") (pin "5") (pinfunction "VDD_5") (pintype "bidirectional"))
      (node (ref "U5") (pin "4") (pinfunction "V+_4") (pintype "power_in"))
      (node (ref "U6") (pin "3") (pinfunction "VDD_3") (pintype "bidirectional"))
      (node (ref "U6") (pin "5") (pinfunction "VDD_5") (pintype "bidirectional"))
      (node (ref "U7") (pin "4") (pinfunction "VCC_4") (pintype "power_in"))
      (node (ref "U9") (pin "16") (pinfunction "VCC_16") (pintype "power_in"))
    )
    (net (code "3") (name "+12V") (class "Default")
      (node (ref "BUZZ1") (pin "P$1") (pinfunction "P$1_P$1") (pintype "bidirectional"))
      (node (ref "J2") (pin "1") (pinfunction "1_1") (pintype "passive"))
      (node (ref "R3") (pin "P$2") (pinfunction "2_P$2") (pintype "passive"))
      (node (ref "R9") (pin "2") (pinfunction "2_2") (pintype "passive"))
      (node (ref "SAM_CONN") (pin "P$6") (pinfunction "S_P$6") (pintype "passive"))
    )
    (net (code "4") (name "+24V") (class "Default")
      (node (ref "R7") (pin "2") (pinfunction "2_2") (pintype "passive"))
      (node (ref "SAM_CONN") (pin "P$8") (pinfunction "S_P$8") (pintype "passive"))
    )
    (net (code "5") (name "AN3") (class "Default")
      (node (ref "IC1") (pin "22") (pinfunction "RB3/AN3/CN5/INDX_22") (pintype "bidirectional"))
      (node (ref "R6") (pin "2") (pinfunction "2_2") (pintype "passive"))
      (node (ref "R7") (pin "1") (pinfunction "1_1") (pintype "passive"))
    )
    (net (code "6") (name "AN4") (class "Default")
      (node (ref "IC1") (pin "23") (pinfunction "RB4/AN4/CN6/IC7/QEA_23") (pintype "bidirectional"))
      (node (ref "R8") (pin "2") (pinfunction "2_2") (pintype "passive"))
      (node (ref "R9") (pin "1") (pinfunction "1_1") (pintype "passive"))
    )
    (net (code "7") (name "AN5") (class "Default")
      (node (ref "IC1") (pin "24") (pinfunction "RB5/AN5/CN7/IC8/QEB_24") (pintype "bidirectional"))
      (node (ref "R10") (pin "2") (pinfunction "2_2") (pintype "passive"))
      (node (ref "R11") (pin "1") (pinfunction "1_1") (pintype "passive"))
    )
    (net (code "8") (name "CAP_B") (class "Default")
      (node (ref "IC1") (pin "5") (pinfunction "C1RX/RF0_5") (pintype "bidirectional"))
      (node (ref "R1") (pin "2") (pinfunction "2_2") (pintype "passive"))
      (node (ref "R2") (pin "1") (pinfunction "1_1") (pintype "passive"))
    )
    (net (code "9") (name "DIPSW1") (class "Default")
      (node (ref "C11") (pin "1") (pinfunction "1_1") (pintype "passive"))
      (node (ref "J3") (pin "1") (pinfunction "A1_1") (pintype "passive"))
      (node (ref "R21") (pin "1") (pinfunction "1_1") (pintype "passive"))
      (node (ref "R23") (pin "1") (pinfunction "1_1") (pintype "passive"))
      (node (ref "U10") (pin "5") (pinfunction "EN_5") (pintype "input"))
    )
    (net (code "10") (name "DOUT") (class "Default")
      (node (ref "IC1") (pin "41") (pinfunction "RD2/OC3_41") (pintype "bidirectional"))
      (node (ref "MOLEX20") (pin "6") (pinfunction "6_6") (pintype "bidirectional"))
    )
    (net (code "11") (name "EN12") (class "Default")
      (node (ref "IC1") (pin "27") (pinfunction "RB8/AN8_27") (pintype "bidirectional"))
      (node (ref "SAM_CONN") (pin "P$17") (pinfunction "S_P$17") (pintype "passive"))
    )
    (net (code "12") (name "EN24") (class "Default")
      (node (ref "IC1") (pin "26") (pinfunction "RB7/AN7_26") (pintype "bidirectional"))
      (node (ref "SAM_CONN") (pin "P$15") (pinfunction "S_P$15") (pintype "passive"))
    )
    (net (code "13") (name "EN_AN") (class "Default")
      (node (ref "IC1") (pin "11") (pinfunction "PWM2L/RE2_11") (pintype "bidirectional"))
      (node (ref "R16") (pin "1") (pinfunction "1_1") (pintype "passive"))
      (node (ref "R17") (pin "1") (pinfunction "1_1") (pintype "passive"))
      (node (ref "R18") (pin "1") (pinfunction "1_1") (pintype "passive"))
    )
    (net (code "14") (name "EN_VBAT") (class "Default")
      (node (ref "IC1") (pin "31") (pinfunction "OSC2/CLKO/RC15_31") (pintype "bidirectional"))
      (node (ref "SAM_CONN") (pin "P$19") (pinfunction "S_P$19") (pintype "passive"))
    )
    (net (code "15") (name "FAN_A") (class "Default")
      (node (ref "IC1") (pin "37") (pinfunction "RD1/INT2/IC2/OC2/EMUD2_37") (pintype "bidirectional"))
      (node (ref "SAM_CONN") (pin "P$13") (pinfunction "S_P$13") (pintype "passive"))
    )
    (net (code "16") (name "FAN_B") (class "Default")
      (node (ref "IC1") (pin "38") (pinfunction "RD3/OC4_38") (pintype "bidirectional"))
      (node (ref "SAM_CONN") (pin "P$11") (pinfunction "S_P$11") (pintype "passive"))
    )
    (net (code "17") (name "GND") (class "Default")
      (node (ref "C1") (pin "2") (pinfunction "2_2") (pintype "passive"))
      (node (ref "C10") (pin "2") (pinfunction "2_2") (pintype "passive"))
      (node (ref "C11") (pin "2") (pinfunction "2_2") (pintype "passive"))
      (node (ref "C13") (pin "2") (pinfunction "2_2") (pintype "passive"))
      (node (ref "C14") (pin "2") (pinfunction "2_2") (pintype "passive"))
      (node (ref "C15") (pin "2") (pinfunction "2_2") (pintype "passive"))
      (node (ref "C16") (pin "2") (pinfunction "2_2") (pintype "passive"))
      (node (ref "C18") (pin "C") (pinfunction "-_C") (pintype "passive"))
      (node (ref "C19") (pin "2") (pinfunction "2_2") (pintype "passive"))
      (node (ref "C2") (pin "2") (pinfunction "2_2") (pintype "passive"))
      (node (ref "C20") (pin "2") (pinfunction "2_2") (pintype "passive"))
      (node (ref "C21") (pin "2") (pinfunction "2_2") (pintype "passive"))
      (node (ref "C22") (pin "2") (pinfunction "2_2") (pintype "passive"))
      (node (ref "C23") (pin "2") (pinfunction "2_2") (pintype "passive"))
      (node (ref "C24") (pin "2") (pinfunction "2_2") (pintype "passive"))
      (node (ref "C25") (pin "2") (pinfunction "2_2") (pintype "passive"))
      (node (ref "C27") (pin "2") (pinfunction "2_2") (pintype "passive"))
      (node (ref "C28") (pin "2") (pinfunction "-_2") (pintype "passive"))
      (node (ref "C3") (pin "2") (pinfunction "2_2") (pintype "passive"))
      (node (ref "C4") (pin "2") (pinfunction "2_2") (pintype "passive"))
      (node (ref "C5") (pin "2") (pinfunction "2_2") (pintype "passive"))
      (node (ref "C6") (pin "-") (pinfunction "-_-") (pintype "passive"))
      (node (ref "C7") (pin "2") (pinfunction "2_2") (pintype "passive"))
      (node (ref "C8") (pin "2") (pinfunction "-_2") (pintype "passive"))
      (node (ref "IC1") (pin "16") (pinfunction "AVSS_16") (pintype "power_in"))
      (node (ref "IC1") (pin "29") (pinfunction "VSS_29") (pintype "power_in"))
      (node (ref "IC1") (pin "39") (pinfunction "VSS_39") (pintype "power_in"))
      (node (ref "IC1") (pin "6") (pinfunction "VSS_6") (pintype "power_in"))
      (node (ref "J1") (pin "3") (pinfunction "3_3") (pintype "passive"))
      (node (ref "J2") (pin "3") (pinfunction "3_3") (pintype "passive"))
      (node (ref "J4") (pin "3") (pinfunction "3_3") (pintype "passive"))
      (node (ref "MOLEX10") (pin "4") (pinfunction "4_4") (pintype "bidirectional"))
      (node (ref "MOLEX20") (pin "10") (pinfunction "10_10") (pintype "bidirectional"))
      (node (ref "MOLEX20") (pin "11") (pinfunction "11_11") (pintype "bidirectional"))
      (node (ref "MOLEX20") (pin "12") (pinfunction "12_12") (pintype "bidirectional"))
      (node (ref "MOLEX20") (pin "17") (pinfunction "17_17") (pintype "bidirectional"))
      (node (ref "MOLEX20") (pin "3") (pinfunction "3_3") (pintype "bidirectional"))
      (node (ref "NUC_CONN") (pin "5") (pinfunction "S_5") (pintype "passive"))
      (node (ref "NUC_CONN") (pin "8") (pinfunction "S_8") (pintype "passive"))
      (node (ref "Q1") (pin "NC") (pinfunction "E_NC") (pintype "passive"))
      (node (ref "Q3") (pin "NC") (pinfunction "E_NC") (pintype "passive"))
      (node (ref "Q4") (pin "NC") (pinfunction "E_NC") (pintype "passive"))
      (node (ref "Q5") (pin "NC") (pinfunction "E_NC") (pintype "passive"))
      (node (ref "R1") (pin "1") (pinfunction "1_1") (pintype "passive"))
      (node (ref "S2") (pin "1") (pinfunction "1_1") (pintype "passive"))
      (node (ref "S3") (pin "1") (pinfunction "1_1") (pintype "passive"))
      (node (ref "SAM_CONN") (pin "P$1") (pinfunction "S_P$1") (pintype "passive"))
      (node (ref "SAM_CONN") (pin "P$14") (pinfunction "S_P$14") (pintype "passive"))
      (node (ref "SAM_CONN") (pin "P$2") (pinfunction "S_P$2") (pintype "passive"))
      (node (ref "U1") (pin "18") (pinfunction "GND18_18") (pintype "power_in"))
      (node (ref "U1") (pin "21") (pinfunction "GND21_21") (pintype "power_in"))
      (node (ref "U1") (pin "25") (pinfunction "AGND_25") (pintype "power_in"))
      (node (ref "U1") (pin "26") (pinfunction "TEST_26") (pintype "input"))
      (node (ref "U1") (pin "7") (pinfunction "GND7_7") (pintype "power_in"))
      (node (ref "U10") (pin "4") (pinfunction "GND_4") (pintype "passive"))
      (node (ref "U11") (pin "14") (pinfunction "VSS_14") (pintype "passive"))
      (node (ref "U2") (pin "6") (pinfunction "VSS_6") (pintype "bidirectional"))
      (node (ref "U3") (pin "6") (pinfunction "VSS_6") (pintype "bidirectional"))
      (node (ref "U4") (pin "6") (pinfunction "VSS_6") (pintype "bidirectional"))
      (node (ref "U5") (pin "2") (pinfunction "GND_2") (pintype "power_in"))
      (node (ref "U5") (pin "3") (pinfunction "ADD1_3") (pintype "input"))
      (node (ref "U5") (pin "5") (pinfunction "ADD0_5") (pintype "input"))
      (node (ref "U6") (pin "6") (pinfunction "VSS_6") (pintype "bidirectional"))
      (node (ref "U7") (pin "11") (pinfunction "GND_11") (pintype "passive"))
      (node (ref "U8") (pin "6") (pinfunction "GND_6") (pintype "bidirectional"))
      (node (ref "U9") (pin "1") (pinfunction "A0_1") (pintype "input"))
      (node (ref "U9") (pin "13") (pinfunction "A2_13") (pintype "input"))
      (node (ref "U9") (pin "2") (pinfunction "A1_2") (pintype "input"))
      (node (ref "U9") (pin "8") (pinfunction "GND_8") (pintype "power_in"))
      (node (ref "USB") (pin "1") (pinfunction "1_1") (pintype "passive"))
    )
    (net (code "18") (name "GP_OUT") (class "Default")
      (node (ref "IC1") (pin "3") (pinfunction "CN17/U2RX/RF4_3") (pintype "bidirectional"))
      (node (ref "MOLEX20") (pin "16") (pinfunction "16_16") (pintype "bidirectional"))
    )
    (net (code "19") (name "HDD_LED#") (class "Default")
      (node (ref "NUC_CONN") (pin "3") (pinfunction "S_3") (pintype "passive"))
    )
    (net (code "20") (name "HDD_POWER_LED") (class "Default")
      (node (ref "NUC_CONN") (pin "1") (pinfunction "S_1") (pintype "passive"))
    )
    (net (code "21") (name "I5") (class "Default")
      (node (ref "IC1") (pin "19") (pinfunction "RB0/AN0/CN2/EMUD3/VR+_19") (pintype "bidirectional"))
      (node (ref "U7") (pin "1") (pinfunction "1OUT_1") (pintype "output"))
      (node (ref "U7") (pin "2") (pinfunction "1IN-_2") (pintype "input"))
    )
    (net (code "22") (name "I5M") (class "Default")
      (node (ref "SAM_CONN") (pin "P$20") (pinfunction "S_P$20") (pintype "passive"))
      (node (ref "U7") (pin "3") (pinfunction "1IN+_3") (pintype "input"))
    )
    (net (code "23") (name "I12") (class "Default")
      (node (ref "IC1") (pin "20") (pinfunction "RB1/AN1/CN3/EMUC3/VR-_20") (pintype "bidirectional"))
      (node (ref "U7") (pin "8") (pinfunction "3OUT_8") (pintype "output"))
      (node (ref "U7") (pin "9") (pinfunction "3IN-_9") (pintype "input"))
    )
    (net (code "24") (name "I12M") (class "Default")
      (node (ref "SAM_CONN") (pin "P$18") (pinfunction "S_P$18") (pintype "passive"))
      (node (ref "U7") (pin "10") (pinfunction "3IN+_10") (pintype "input"))
    )
    (net (code "25") (name "I24") (class "Default")
      (node (ref "IC1") (pin "21") (pinfunction "RB2/AN2/CN4/SS1_21") (pintype "bidirectional"))
      (node (ref "U7") (pin "6") (pinfunction "2IN-_6") (pintype "input"))
      (node (ref "U7") (pin "7") (pinfunction "2OUT_7") (pintype "output"))
    )
    (net (code "26") (name "I24M") (class "Default")
      (node (ref "SAM_CONN") (pin "P$16") (pinfunction "S_P$16") (pintype "passive"))
      (node (ref "U7") (pin "5") (pinfunction "2IN+_5") (pintype "input"))
    )
    (net (code "27") (name "ICSPCLK") (class "Default")
      (node (ref "J4") (pin "5") (pinfunction "5_5") (pintype "passive"))
      (node (ref "U11") (pin "12") (pinfunction "RB1/AN1/C1IN-/ICSPCLK_12") (pintype "passive"))
    )
    (net (code "28") (name "ICSPDAT") (class "Default")
      (node (ref "J4") (pin "4") (pinfunction "4_4") (pintype "passive"))
      (node (ref "U11") (pin "13") (pinfunction "RB0/AN0/C1IN+/ICSPDAT_13") (pintype "passive"))
    )
    (net (code "29") (name "INT") (class "Default")
      (node (ref "R32") (pin "1") (pinfunction "1_1") (pintype "passive"))
      (node (ref "U8") (pin "2") (pinfunction "INT_2") (pintype "bidirectional"))
    )
    (net (code "30") (name "INT_LUZ") (class "Default")
      (node (ref "IC1") (pin "2") (pinfunction "CN18/U2TX/RF5_2") (pintype "bidirectional"))
      (node (ref "MOLEX20") (pin "15") (pinfunction "15_15") (pintype "bidirectional"))
    )
    (net (code "31") (name "LED1") (class "Default")
      (node (ref "IC1") (pin "42") (pinfunction "RD0/INT1/IC1/OC1/EMUC2_42") (pintype "bidirectional"))
      (node (ref "MOLEX20") (pin "19") (pinfunction "19_19") (pintype "bidirectional"))
    )
    (net (code "32") (name "LED2") (class "Default")
      (node (ref "IC1") (pin "43") (pinfunction "SCK1/RF6_43") (pintype "bidirectional"))
      (node (ref "MOLEX20") (pin "20") (pinfunction "20_20") (pintype "bidirectional"))
    )
    (net (code "33") (name "MCLK") (class "Default")
      (node (ref "MOLEX20") (pin "7") (pinfunction "7_7") (pintype "bidirectional"))
      (node (ref "U11") (pin "8") (pinfunction "RC2/CVREF_8") (pintype "passive"))
    )
    (net (code "34") (name "MCLR") (class "Default")
      (node (ref "C8") (pin "1") (pinfunction "+_1") (pintype "passive"))
      (node (ref "IC1") (pin "18") (pinfunction "VPP/MCLR_18") (pintype "input"))
      (node (ref "J1") (pin "1") (pinfunction "1_1") (pintype "passive"))
      (node (ref "R20") (pin "1") (pinfunction "1_1") (pintype "passive"))
      (node (ref "S2") (pin "2") (pinfunction "2_2") (pintype "passive"))
    )
    (net (code "35") (name "MCLR_2") (class "Default")
      (node (ref "C28") (pin "1") (pinfunction "+_1") (pintype "passive"))
      (node (ref "J4") (pin "1") (pinfunction "1_1") (pintype "passive"))
      (node (ref "R14") (pin "1") (pinfunction "1_1") (pintype "passive"))
      (node (ref "S3") (pin "2") (pinfunction "2_2") (pintype "passive"))
      (node (ref "U11") (pin "4") (pinfunction "RB3/~{MCLR/VPP}_4") (pintype "passive"))
    )
    (net (code "36") (name "NUC_SW") (class "Default")
      (node (ref "IC1") (pin "8") (pinfunction "PWM3H/RE5_8") (pintype "bidirectional"))
      (node (ref "R5") (pin "1") (pinfunction "1_1") (pintype "passive"))
    )
    (net (code "37") (name "Net-(D1-Pad2)") (class "Default")
      (node (ref "D1") (pin "2") (pinfunction "2_2") (pintype "passive"))
      (node (ref "R12") (pin "1") (pinfunction "1_1") (pintype "passive"))
    )
    (net (code "38") (name "Net-(D2-Pad2)") (class "Default")
      (node (ref "D2") (pin "2") (pinfunction "2_2") (pintype "passive"))
      (node (ref "R13") (pin "1") (pinfunction "1_1") (pintype "passive"))
    )
    (net (code "39") (name "Net-(D3-Pad1)") (class "Default")
      (node (ref "D3") (pin "1") (pinfunction "1_1") (pintype "passive"))
      (node (ref "R19") (pin "1") (pinfunction "1_1") (pintype "passive"))
    )
    (net (code "40") (name "Net-(J2-Pad2)") (class "Default")
      (node (ref "J2") (pin "2") (pinfunction "2_2") (pintype "passive"))
      (node (ref "R2") (pin "2") (pinfunction "2_2") (pintype "passive"))
    )
    (net (code "41") (name "Net-(Q1-B)") (class "Default")
      (node (ref "Q1") (pin "A") (pinfunction "B_A") (pintype "passive"))
      (node (ref "R4") (pin "1") (pinfunction "1_1") (pintype "passive"))
    )
    (net (code "42") (name "Net-(Q3-B)") (class "Default")
      (node (ref "Q3") (pin "A") (pinfunction "B_A") (pintype "passive"))
      (node (ref "R16") (pin "2") (pinfunction "2_2") (pintype "passive"))
    )
    (net (code "43") (name "Net-(Q3-PadC)") (class "Default")
      (node (ref "Q3") (pin "C") (pinfunction "C_C") (pintype "passive"))
      (node (ref "R6") (pin "1") (pinfunction "1_1") (pintype "passive"))
    )
    (net (code "44") (name "Net-(Q4-B)") (class "Default")
      (node (ref "Q4") (pin "A") (pinfunction "B_A") (pintype "passive"))
      (node (ref "R17") (pin "2") (pinfunction "2_2") (pintype "passive"))
    )
    (net (code "45") (name "Net-(Q4-PadC)") (class "Default")
      (node (ref "Q4") (pin "C") (pinfunction "C_C") (pintype "passive"))
      (node (ref "R8") (pin "1") (pinfunction "1_1") (pintype "passive"))
    )
    (net (code "46") (name "Net-(Q5-B)") (class "Default")
      (node (ref "Q5") (pin "A") (pinfunction "B_A") (pintype "passive"))
      (node (ref "R18") (pin "2") (pinfunction "2_2") (pintype "passive"))
    )
    (net (code "47") (name "Net-(Q5-PadC)") (class "Default")
      (node (ref "Q5") (pin "C") (pinfunction "C_C") (pintype "passive"))
      (node (ref "R10") (pin "1") (pinfunction "1_1") (pintype "passive"))
    )
    (net (code "48") (name "Net-(R3-1)") (class "Default")
      (node (ref "BUZZ1") (pin "P$2") (pinfunction "P$2_P$2") (pintype "bidirectional"))
      (node (ref "Q1") (pin "C") (pinfunction "C_C") (pintype "passive"))
      (node (ref "R3") (pin "P$1") (pinfunction "1_P$1") (pintype "passive"))
    )
    (net (code "49") (name "Net-(U1-3V3OUT)") (class "Default")
      (node (ref "C4") (pin "1") (pinfunction "1_1") (pintype "passive"))
      (node (ref "U1") (pin "17") (pinfunction "3V3OUT_17") (pintype "output"))
    )
    (net (code "50") (name "Net-(U1-RXLED)") (class "Default")
      (node (ref "D2") (pin "1") (pinfunction "1_1") (pintype "passive"))
      (node (ref "U1") (pin "22") (pinfunction "RXLED_22") (pintype "input"))
    )
    (net (code "51") (name "Net-(U1-TXLED)") (class "Default")
      (node (ref "D1") (pin "1") (pinfunction "1_1") (pintype "passive"))
      (node (ref "U1") (pin "23") (pinfunction "TXLED_23") (pintype "input"))
    )
    (net (code "52") (name "Net-(U1-USBDM)") (class "Default")
      (node (ref "U1") (pin "16") (pinfunction "USBDM_16") (pintype "bidirectional"))
      (node (ref "USB") (pin "3") (pinfunction "3_3") (pintype "passive"))
    )
    (net (code "53") (name "Net-(U1-USBDP)") (class "Default")
      (node (ref "U1") (pin "15") (pinfunction "USBDP_15") (pintype "bidirectional"))
      (node (ref "USB") (pin "2") (pinfunction "2_2") (pintype "passive"))
    )
    (net (code "54") (name "Net-(U2-DO)") (class "Default")
      (node (ref "U2") (pin "1") (pinfunction "DO_1") (pintype "bidirectional"))
      (node (ref "U3") (pin "2") (pinfunction "DI_2") (pintype "bidirectional"))
    )
    (net (code "55") (name "Net-(U3-DO)") (class "Default")
      (node (ref "U3") (pin "1") (pinfunction "DO_1") (pintype "bidirectional"))
      (node (ref "U4") (pin "2") (pinfunction "DI_2") (pintype "bidirectional"))
    )
    (net (code "56") (name "Net-(U4-DO)") (class "Default")
      (node (ref "U4") (pin "1") (pinfunction "DO_1") (pintype "bidirectional"))
      (node (ref "U6") (pin "2") (pinfunction "DI_2") (pintype "bidirectional"))
    )
    (net (code "57") (name "Net-(U8-LDR)") (class "Default")
      (node (ref "U8") (pin "3") (pinfunction "LDR_3") (pintype "bidirectional"))
      (node (ref "U8") (pin "4") (pinfunction "LEDK_4") (pintype "bidirectional"))
    )
    (net (code "58") (name "Net-(U9-~{RESET})") (class "Default")
      (node (ref "R15") (pin "1") (pinfunction "1_1") (pintype "passive"))
      (node (ref "U9") (pin "3") (pinfunction "~{RESET}_3") (pintype "input"))
    )
    (net (code "59") (name "Net-(U11-RB4{slash}OSC2{slash}CLKOUT)") (class "Default")
      (node (ref "C25") (pin "1") (pinfunction "1_1") (pintype "passive"))
      (node (ref "U11") (pin "3") (pinfunction "RB4/OSC2/CLKOUT_3") (pintype "passive"))
      (node (ref "Y1") (pin "1") (pinfunction "1_1") (pintype "passive"))
    )
    (net (code "60") (name "Net-(U11-RB5{slash}OSC1{slash}CLKIN)") (class "Default")
      (node (ref "C21") (pin "1") (pinfunction "1_1") (pintype "passive"))
      (node (ref "U11") (pin "2") (pinfunction "RB5/OSC1/CLKIN_2") (pintype "passive"))
      (node (ref "Y1") (pin "2") (pinfunction "2_2") (pintype "passive"))
    )
    (net (code "61") (name "POWER_LED_ALT") (class "Default")
      (node (ref "NUC_CONN") (pin "4") (pinfunction "S_4") (pintype "passive"))
    )
    (net (code "62") (name "POWER_LED_MAIN") (class "Default")
      (node (ref "IC1") (pin "9") (pinfunction "PWM3L/RE4_9") (pintype "bidirectional"))
      (node (ref "NUC_CONN") (pin "2") (pinfunction "S_2") (pintype "passive"))
      (node (ref "R19") (pin "2") (pinfunction "2_2") (pintype "passive"))
    )
    (net (code "63") (name "POW_SW") (class "Default")
      (node (ref "NUC_CONN") (pin "6") (pinfunction "S_6") (pintype "passive"))
      (node (ref "R5") (pin "2") (pinfunction "2_2") (pintype "passive"))
    )
    (net (code "64") (name "RESET_SWITCH#") (class "Default")
      (node (ref "NUC_CONN") (pin "7") (pinfunction "S_7") (pintype "passive"))
    )
    (net (code "65") (name "RF2") (class "Default")
      (node (ref "IC1") (pin "1") (pinfunction "PGC/EMUC/SDI1/SDA/U1RX/RF2_1") (pintype "bidirectional"))
      (node (ref "J1") (pin "5") (pinfunction "5_5") (pintype "passive"))
      (node (ref "R23") (pin "2") (pinfunction "2_2") (pintype "passive"))
      (node (ref "U10") (pin "3") (pinfunction "SDA0_3") (pintype "bidirectional"))
    )
    (net (code "66") (name "RF3") (class "Default")
      (node (ref "IC1") (pin "44") (pinfunction "PGD/EMUD/SDO1/SCL/U1TX/RF3_44") (pintype "bidirectional"))
      (node (ref "J1") (pin "4") (pinfunction "4_4") (pintype "passive"))
      (node (ref "R21") (pin "2") (pinfunction "2_2") (pintype "passive"))
      (node (ref "U10") (pin "2") (pinfunction "SCL0_2") (pintype "bidirectional"))
    )
    (net (code "67") (name "RGB_LED") (class "Default")
      (node (ref "IC1") (pin "14") (pinfunction "PWM1H/RE1_14") (pintype "bidirectional"))
      (node (ref "U2") (pin "2") (pinfunction "DI_2") (pintype "bidirectional"))
    )
    (net (code "68") (name "RX1") (class "Default")
      (node (ref "IC1") (pin "35") (pinfunction "RC14/CN0/T1CK/U1ARX/SOSCO/EMUC1_35") (pintype "bidirectional"))
      (node (ref "U1") (pin "1") (pinfunction "TXD_1") (pintype "output"))
    )
    (net (code "69") (name "SCL") (class "Default")
      (node (ref "R25") (pin "1") (pinfunction "1_1") (pintype "passive"))
      (node (ref "U10") (pin "7") (pinfunction "SCL1_7") (pintype "bidirectional"))
      (node (ref "U9") (pin "14") (pinfunction "SCL_14") (pintype "passive"))
    )
    (net (code "70") (name "SCL0") (class "Default")
      (node (ref "MOLEX10") (pin "2") (pinfunction "2_2") (pintype "bidirectional"))
      (node (ref "MOLEX20") (pin "9") (pinfunction "9_9") (pintype "bidirectional"))
      (node (ref "R27") (pin "1") (pinfunction "1_1") (pintype "passive"))
      (node (ref "SAM_CONN") (pin "P$10") (pinfunction "S_P$10") (pintype "passive"))
      (node (ref "U5") (pin "1") (pinfunction "SCL_1") (pintype "input"))
      (node (ref "U9") (pin "5") (pinfunction "SC0_5") (pintype "passive"))
    )
    (net (code "71") (name "SCL1") (class "Default")
      (node (ref "MOLEX20") (pin "4") (pinfunction "4_4") (pintype "bidirectional"))
      (node (ref "R29") (pin "1") (pinfunction "1_1") (pintype "passive"))
      (node (ref "U9") (pin "7") (pinfunction "SC1_7") (pintype "passive"))
    )
    (net (code "72") (name "SCL2") (class "Default")
      (node (ref "MOLEX20") (pin "14") (pinfunction "14_14") (pintype "bidirectional"))
      (node (ref "R31") (pin "1") (pinfunction "1_1") (pintype "passive"))
      (node (ref "U8") (pin "7") (pinfunction "SCL_7") (pintype "bidirectional"))
      (node (ref "U9") (pin "10") (pinfunction "SC2_10") (pintype "passive"))
    )
    (net (code "73") (name "SCL3") (class "Default")
      (node (ref "R34") (pin "1") (pinfunction "1_1") (pintype "passive"))
      (node (ref "SAM_CONN") (pin "P$7") (pinfunction "S_P$7") (pintype "passive"))
      (node (ref "U9") (pin "12") (pinfunction "SC3_12") (pintype "passive"))
    )
    (net (code "74") (name "SDA") (class "Default")
      (node (ref "R22") (pin "1") (pinfunction "1_1") (pintype "passive"))
      (node (ref "U10") (pin "6") (pinfunction "SDA1_6") (pintype "bidirectional"))
      (node (ref "U9") (pin "15") (pinfunction "SDA_15") (pintype "passive"))
    )
    (net (code "75") (name "SDA0") (class "Default")
      (node (ref "MOLEX10") (pin "3") (pinfunction "3_3") (pintype "bidirectional"))
      (node (ref "MOLEX20") (pin "8") (pinfunction "8_8") (pintype "bidirectional"))
      (node (ref "R26") (pin "1") (pinfunction "1_1") (pintype "passive"))
      (node (ref "SAM_CONN") (pin "P$12") (pinfunction "S_P$12") (pintype "passive"))
      (node (ref "U5") (pin "6") (pinfunction "SDA_6") (pintype "bidirectional"))
      (node (ref "U9") (pin "4") (pinfunction "SD0_4") (pintype "passive"))
    )
    (net (code "76") (name "SDA1") (class "Default")
      (node (ref "MOLEX20") (pin "5") (pinfunction "5_5") (pintype "bidirectional"))
      (node (ref "R28") (pin "1") (pinfunction "1_1") (pintype "passive"))
      (node (ref "U9") (pin "6") (pinfunction "SD1_6") (pintype "passive"))
    )
    (net (code "77") (name "SDA2") (class "Default")
      (node (ref "MOLEX20") (pin "13") (pinfunction "13_13") (pintype "bidirectional"))
      (node (ref "R30") (pin "1") (pinfunction "1_1") (pintype "passive"))
      (node (ref "U8") (pin "1") (pinfunction "SDA_1") (pintype "bidirectional"))
      (node (ref "U9") (pin "9") (pinfunction "SD2_9") (pintype "passive"))
    )
    (net (code "78") (name "SDA3") (class "Default")
      (node (ref "R33") (pin "1") (pinfunction "1_1") (pintype "passive"))
      (node (ref "SAM_CONN") (pin "P$9") (pinfunction "S_P$9") (pintype "passive"))
      (node (ref "U9") (pin "11") (pinfunction "SD3_11") (pintype "passive"))
    )
    (net (code "79") (name "SPEAKER") (class "Default")
      (node (ref "IC1") (pin "15") (pinfunction "PWM1L/RE0_15") (pintype "bidirectional"))
      (node (ref "R4") (pin "2") (pinfunction "2_2") (pintype "passive"))
    )
    (net (code "80") (name "TRIGGER_IN+") (class "Default")
      (node (ref "IC1") (pin "4") (pinfunction "C1TX/RF1_4") (pintype "bidirectional"))
      (node (ref "MOLEX20") (pin "18") (pinfunction "18_18") (pintype "bidirectional"))
    )
    (net (code "81") (name "TX1") (class "Default")
      (node (ref "IC1") (pin "32") (pinfunction "RC13/CN1/T2CK/U1ATX/SOSCI/EMUD1_32") (pintype "bidirectional"))
      (node (ref "U1") (pin "5") (pinfunction "RXD_5") (pintype "input"))
    )
    (net (code "82") (name "VBAT") (class "Default")
      (node (ref "IC1") (pin "25") (pinfunction "RB6/AN6/OCFA_25") (pintype "bidirectional"))
      (node (ref "SAM_CONN") (pin "P$5") (pinfunction "S_P$5") (pintype "passive"))
    )
    (net (code "83") (name "WAKE_UP") (class "Default")
      (node (ref "IC1") (pin "36") (pinfunction "FLTA/INT0/RE8_36") (pintype "bidirectional"))
      (node (ref "U11") (pin "7") (pinfunction "RC3_7") (pintype "passive"))
    )
    (net (code "84") (name "unconnected-(IC1-OSC1{slash}CLKI-Pad30)") (class "Default")
      (node (ref "IC1") (pin "30") (pinfunction "OSC1/CLKI_30") (pintype "input"))
    )
    (net (code "85") (name "unconnected-(IC1-PWM2H{slash}RE3-Pad10)") (class "Default")
      (node (ref "IC1") (pin "10") (pinfunction "PWM2H/RE3_10") (pintype "bidirectional"))
    )
    (net (code "86") (name "unconnected-(J1-Pad6)") (class "Default")
      (node (ref "J1") (pin "6") (pinfunction "6_6") (pintype "passive"))
    )
    (net (code "87") (name "unconnected-(J4-Pad6)") (class "Default")
      (node (ref "J4") (pin "6") (pinfunction "6_6") (pintype "passive"))
    )
    (net (code "88") (name "unconnected-(MOLEX10-Pad5)") (class "Default")
      (node (ref "MOLEX10") (pin "5") (pinfunction "5_5") (pintype "bidirectional"))
    )
    (net (code "89") (name "unconnected-(MOLEX10-Pad6)") (class "Default")
      (node (ref "MOLEX10") (pin "6") (pinfunction "6_6") (pintype "bidirectional"))
    )
    (net (code "90") (name "unconnected-(MOLEX10-Pad7)") (class "Default")
      (node (ref "MOLEX10") (pin "7") (pinfunction "7_7") (pintype "bidirectional"))
    )
    (net (code "91") (name "unconnected-(MOLEX10-Pad8)") (class "Default")
      (node (ref "MOLEX10") (pin "8") (pinfunction "8_8") (pintype "bidirectional"))
    )
    (net (code "92") (name "unconnected-(MOLEX10-Pad9)") (class "Default")
      (node (ref "MOLEX10") (pin "9") (pinfunction "9_9") (pintype "bidirectional"))
    )
    (net (code "93") (name "unconnected-(MOLEX10-Pad10)") (class "Default")
      (node (ref "MOLEX10") (pin "10") (pinfunction "10_10") (pintype "bidirectional"))
    )
    (net (code "94") (name "unconnected-(NUC_CONNB-S-Pad10)") (class "Default")
      (node (ref "NUC_CONN") (pin "10") (pinfunction "S_10") (pintype "passive"))
    )
    (net (code "95") (name "unconnected-(NUC_CONNJ-S-Pad9)") (class "Default")
      (node (ref "NUC_CONN") (pin "9") (pinfunction "S_9") (pintype "passive"))
    )
    (net (code "96") (name "unconnected-(U1-CTS-Pad11)") (class "Default")
      (node (ref "U1") (pin "11") (pinfunction "CTS_11") (pintype "input"))
    )
    (net (code "97") (name "unconnected-(U1-DCD-Pad10)") (class "Default")
      (node (ref "U1") (pin "10") (pinfunction "DCD_10") (pintype "input"))
    )
    (net (code "98") (name "unconnected-(U1-DSR-Pad9)") (class "Default")
      (node (ref "U1") (pin "9") (pinfunction "DSR_9") (pintype "input"))
    )
    (net (code "99") (name "unconnected-(U1-DTR-Pad2)") (class "Default")
      (node (ref "U1") (pin "2") (pinfunction "DTR_2") (pintype "output"))
    )
    (net (code "100") (name "unconnected-(U1-OSCI-Pad27)") (class "Default")
      (node (ref "U1") (pin "27") (pinfunction "OSCI_27") (pintype "input"))
    )
    (net (code "101") (name "unconnected-(U1-OSCO-Pad28)") (class "Default")
      (node (ref "U1") (pin "28") (pinfunction "OSCO_28") (pintype "output"))
    )
    (net (code "102") (name "unconnected-(U1-PWREN-Pad14)") (class "Default")
      (node (ref "U1") (pin "14") (pinfunction "PWREN_14") (pintype "input"))
    )
    (net (code "103") (name "unconnected-(U1-RI-Pad6)") (class "Default")
      (node (ref "U1") (pin "6") (pinfunction "RI_6") (pintype "input"))
    )
    (net (code "104") (name "unconnected-(U1-RTS-Pad3)") (class "Default")
      (node (ref "U1") (pin "3") (pinfunction "RTS_3") (pintype "output"))
    )
    (net (code "105") (name "unconnected-(U1-SLEEP-Pad12)") (class "Default")
      (node (ref "U1") (pin "12") (pinfunction "SLEEP_12") (pintype "input"))
    )
    (net (code "106") (name "unconnected-(U1-TXDEN-Pad13)") (class "Default")
      (node (ref "U1") (pin "13") (pinfunction "TXDEN_13") (pintype "input"))
    )
    (net (code "107") (name "unconnected-(U6-DO-Pad1)") (class "Default")
      (node (ref "U6") (pin "1") (pinfunction "DO_1") (pintype "bidirectional"))
    )
    (net (code "108") (name "unconnected-(U7-4IN+-Pad12)") (class "Default")
      (node (ref "U7") (pin "12") (pinfunction "4IN+_12") (pintype "input"))
    )
    (net (code "109") (name "unconnected-(U7-4IN--Pad13)") (class "Default")
      (node (ref "U7") (pin "13") (pinfunction "4IN-_13") (pintype "input"))
    )
    (net (code "110") (name "unconnected-(U7-4OUT-Pad14)") (class "Default")
      (node (ref "U7") (pin "14") (pinfunction "4OUT_14") (pintype "output"))
    )
    (net (code "111") (name "unconnected-(U10-N.C.-Pad1)") (class "Default")
      (node (ref "U10") (pin "1") (pinfunction "N.C._1") (pintype "no_connect"))
    )
    (net (code "112") (name "unconnected-(U11-RB2{slash}AN2{slash}C1OUT-Pad11)") (class "Default")
      (node (ref "U11") (pin "11") (pinfunction "RB2/AN2/C1OUT_11") (pintype "passive"))
    )
    (net (code "113") (name "unconnected-(U11-RC0{slash}C2IN+-Pad10)") (class "Default")
      (node (ref "U11") (pin "10") (pinfunction "RC0/C2IN+_10") (pintype "passive"))
    )
    (net (code "114") (name "unconnected-(U11-RC1{slash}C2IN--Pad9)") (class "Default")
      (node (ref "U11") (pin "9") (pinfunction "RC1/C2IN-_9") (pintype "passive"))
    )
    (net (code "115") (name "unconnected-(U11-RC4{slash}C2OUT-Pad6)") (class "Default")
      (node (ref "U11") (pin "6") (pinfunction "RC4/C2OUT_6") (pintype "passive"))
    )
    (net (code "116") (name "unconnected-(U11-RC5{slash}T0CKI-Pad5)") (class "Default")
      (node (ref "U11") (pin "5") (pinfunction "RC5/T0CKI_5") (pintype "passive"))
    )
    (net (code "117") (name "unconnected-(USB-Pad4)") (class "Default")
      (node (ref "USB") (pin "4") (pinfunction "4_4") (pintype "passive"))
    )
  )
)
